# Nixie_Clock_v1_05.net
KiCad netlist of a schematic drawn in EAGLE
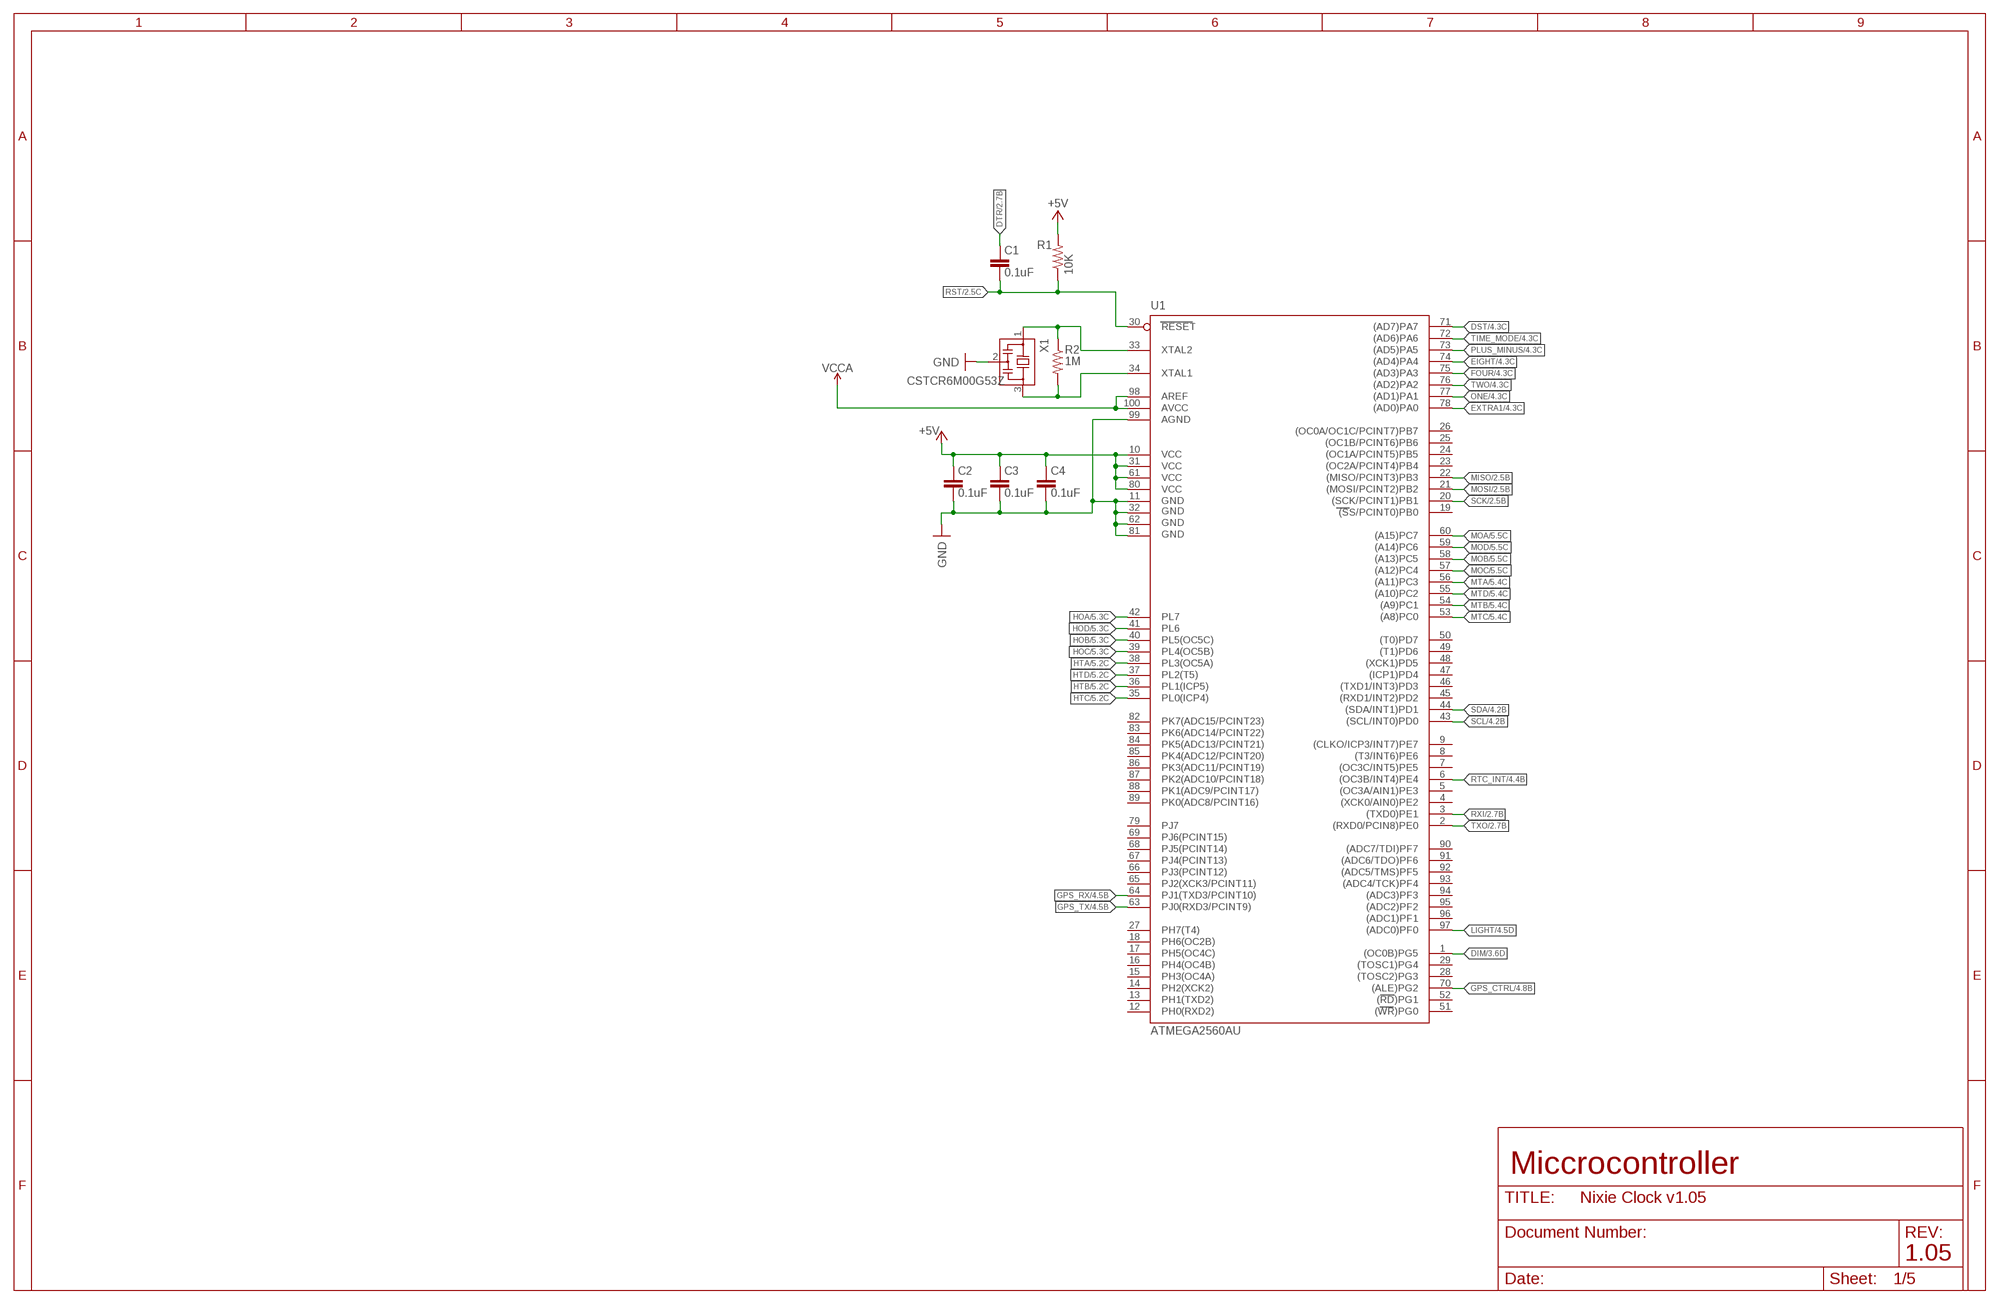
[diagram p0: schematic, sheet 1]
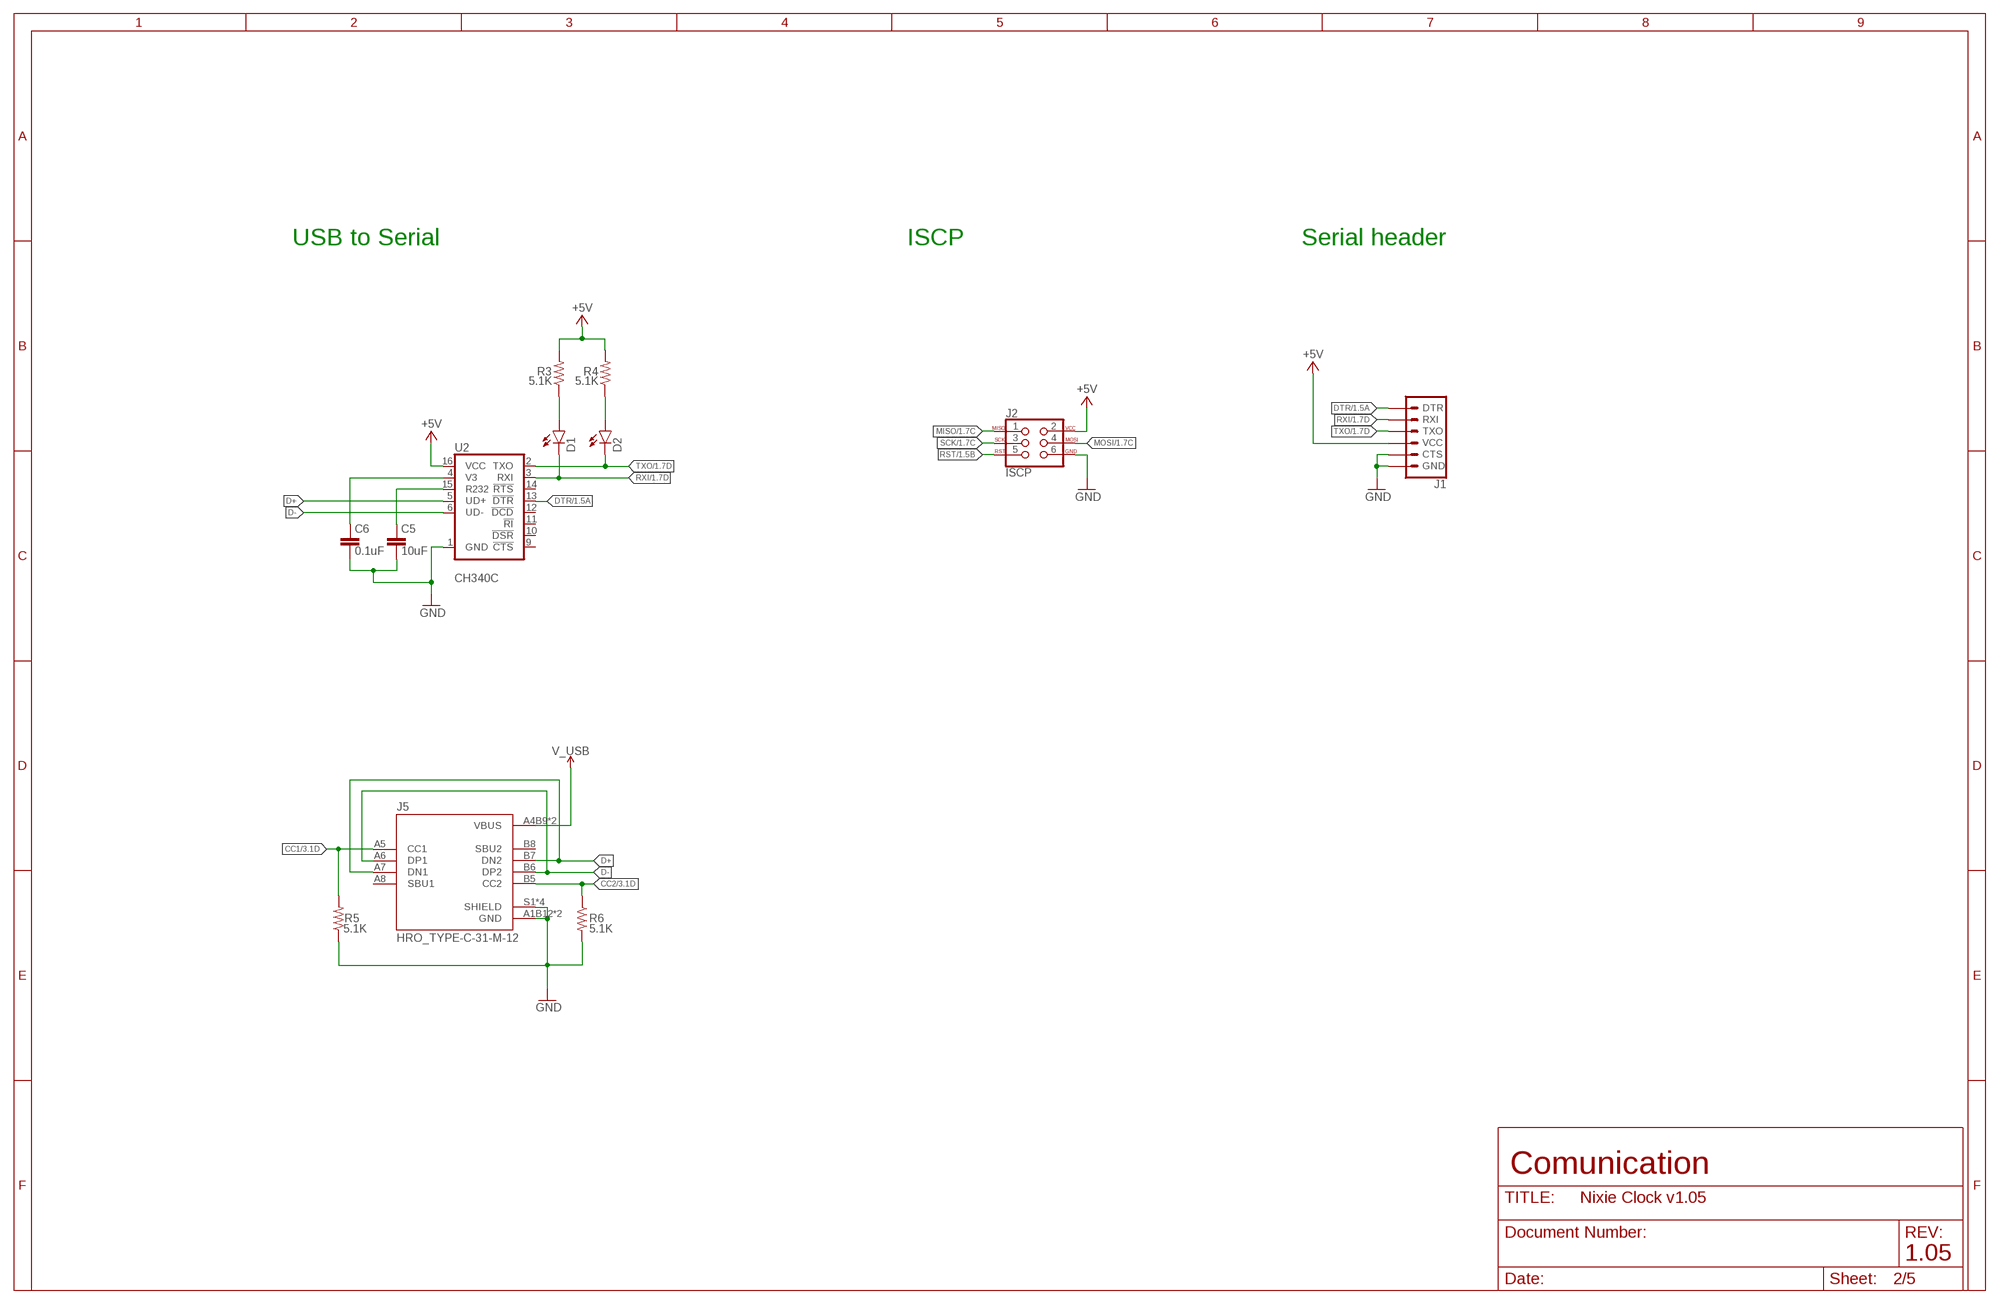
[diagram p1: schematic, sheet 2]
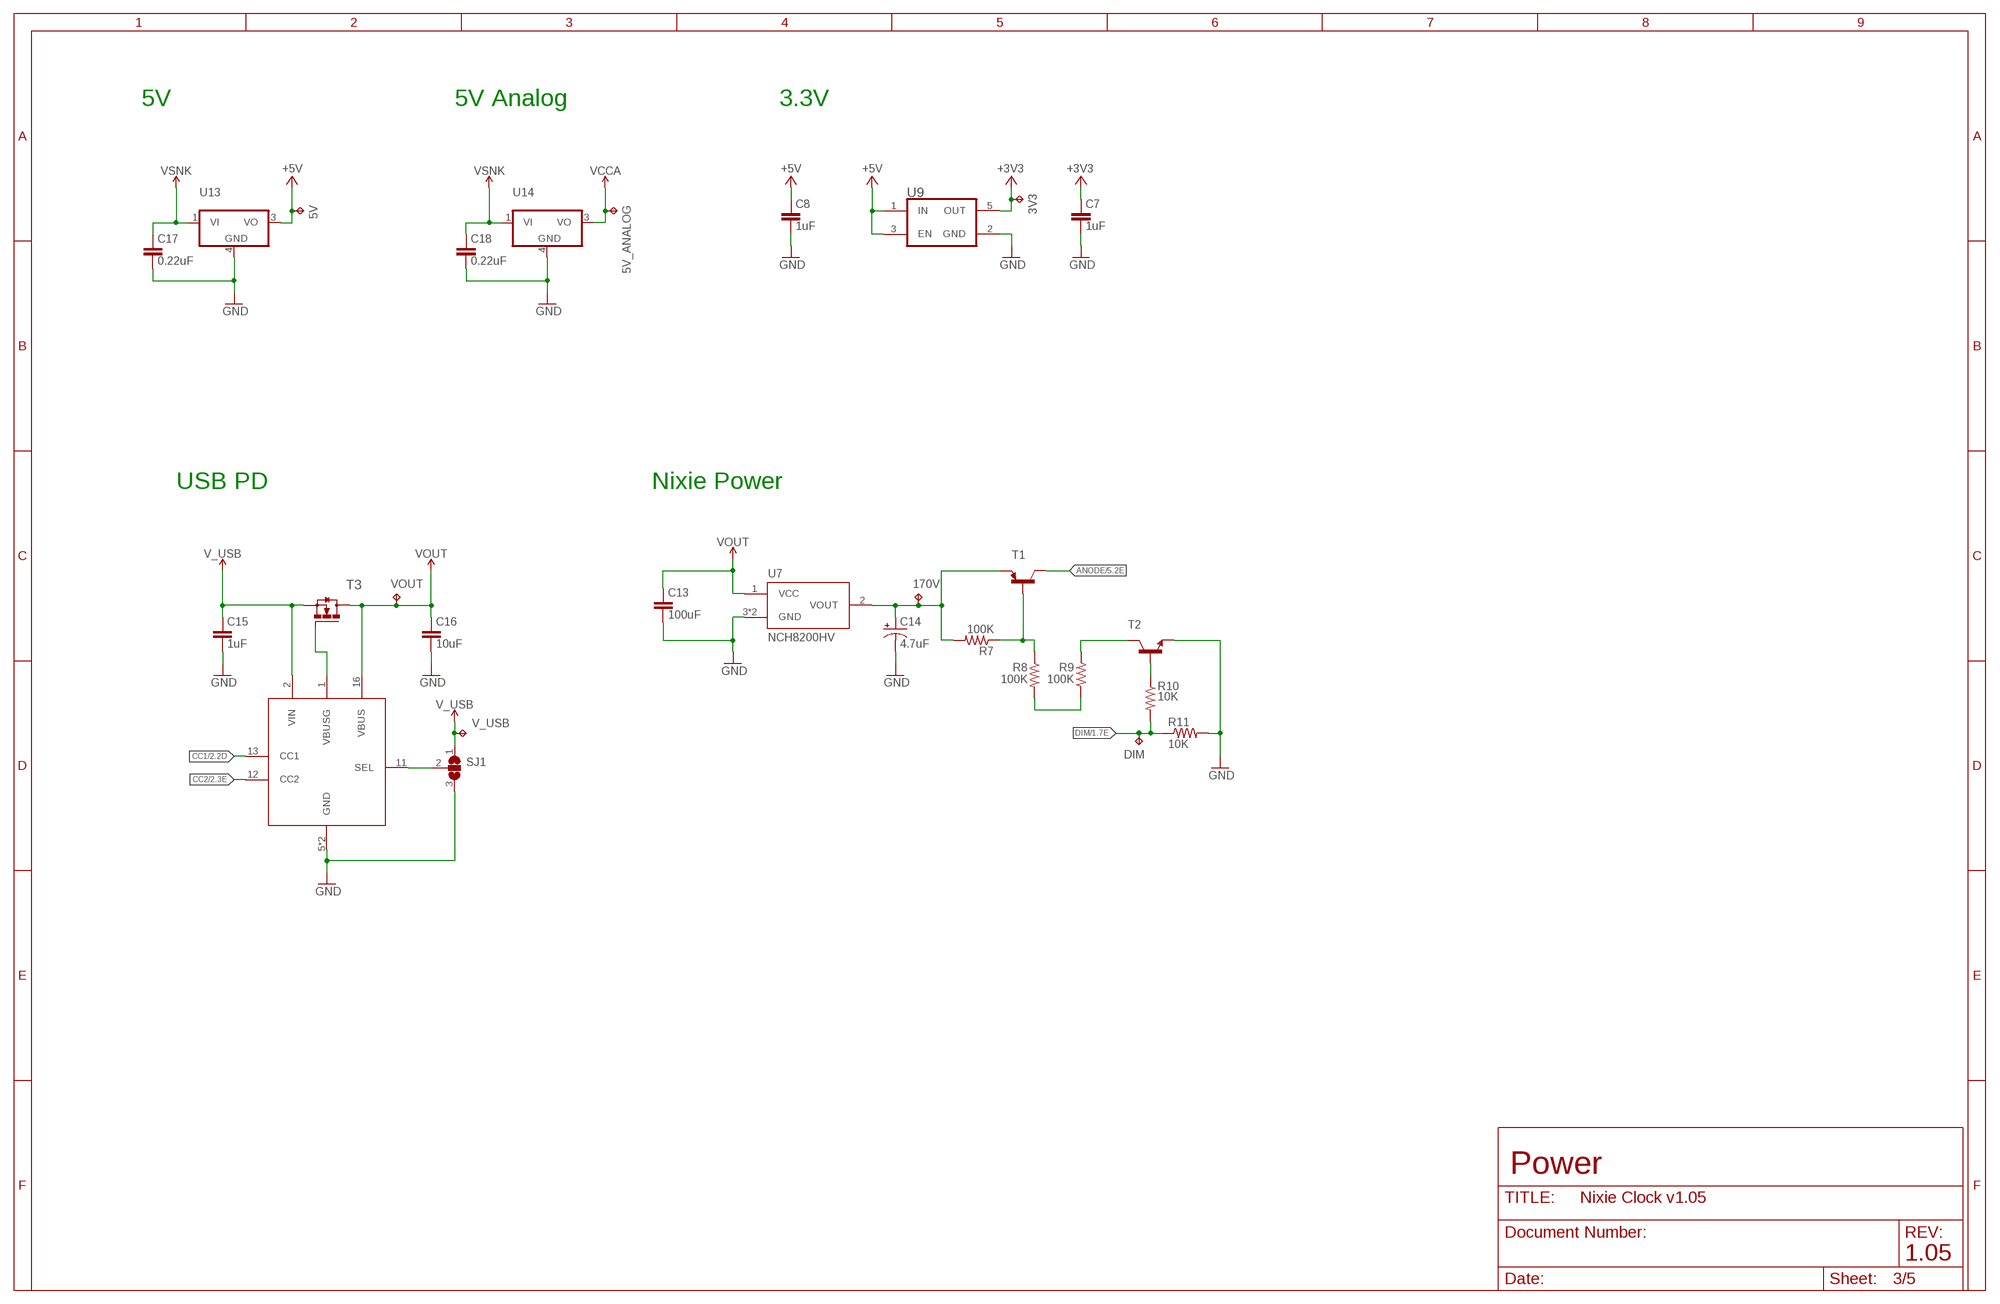
[diagram p2: schematic, sheet 3]
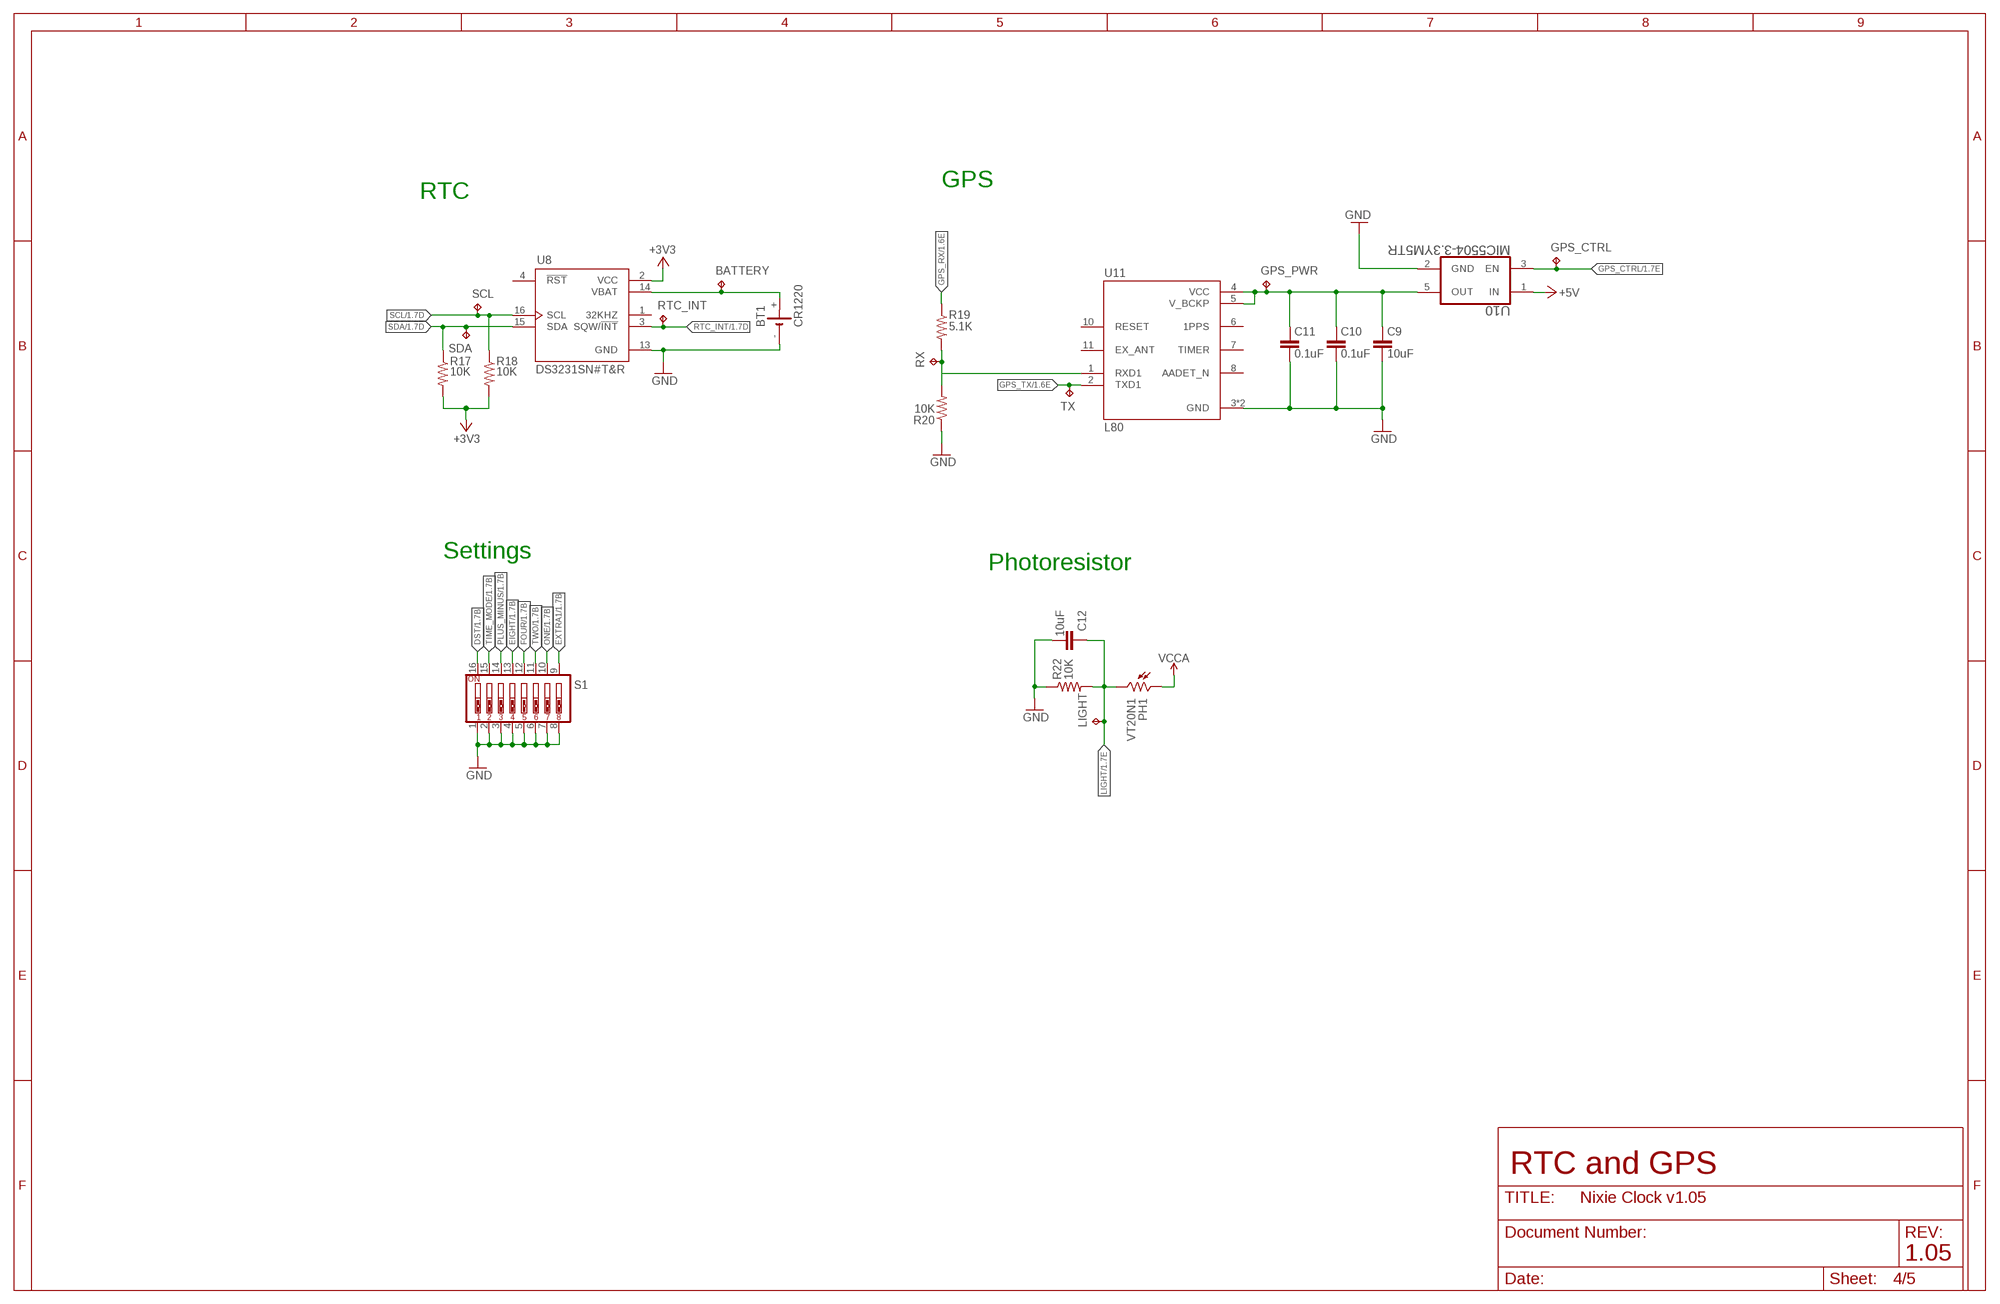
[diagram p3: schematic, sheet 4]
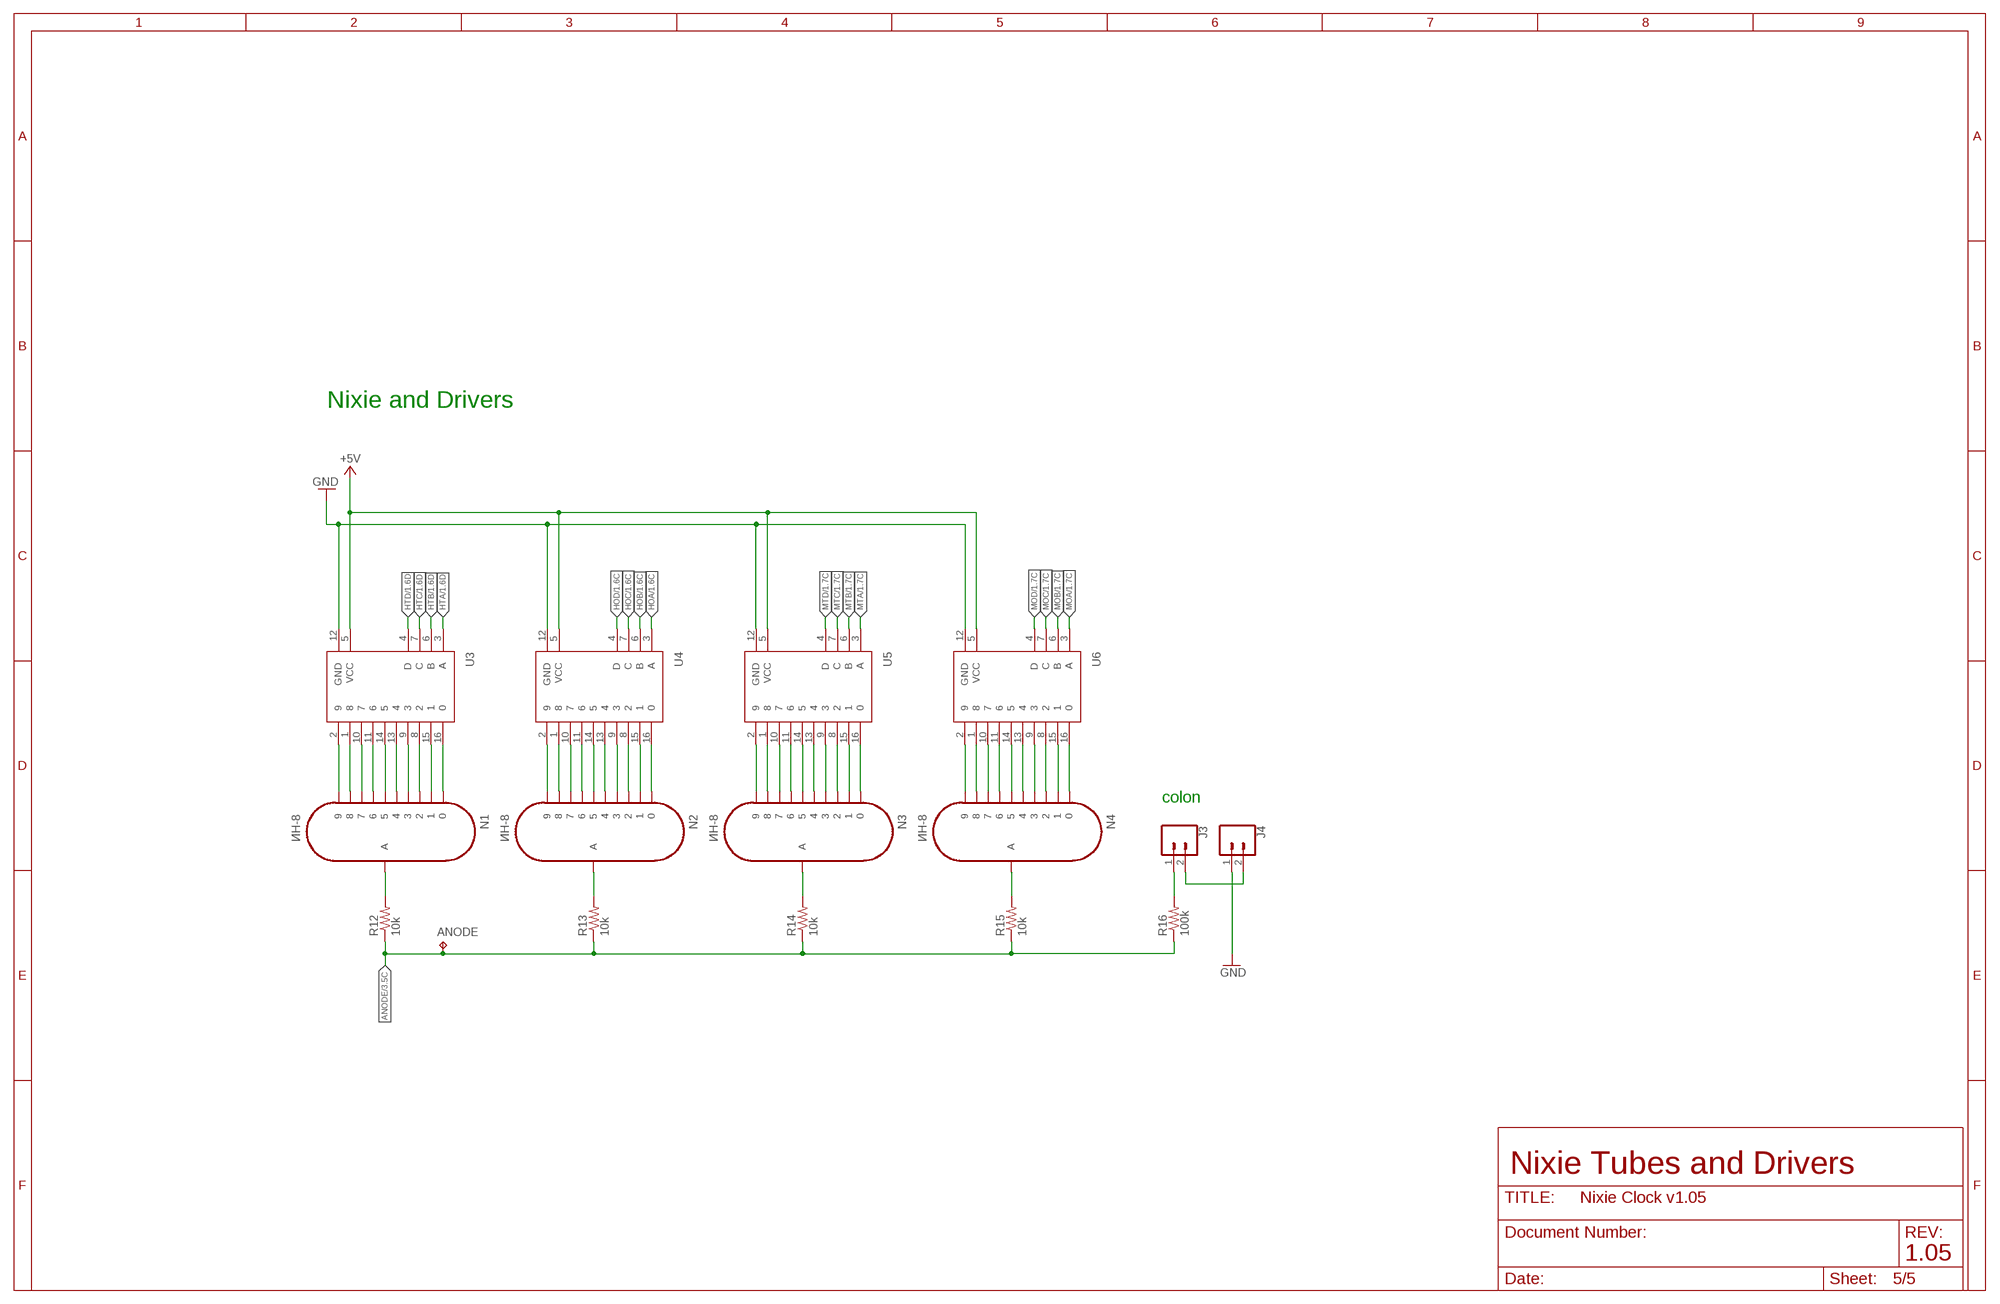
[diagram p4: schematic, sheet 5]

(export (version "E")
  (design (tool "Eeschema 10.0.6"))
  (components
    (comp (ref "ANODE")
      (value "TPPAD1-13")
      (footprint "eagle-import:P1-13")
      (libsource (lib "eagle-import") (part "TPPAD1-13"))
    )
    (comp (ref "J3")
      (value "CONN_02LOCK_LONGPADS")
      (footprint "eagle-import:1X02_LOCK_LONGPADS")
      (libsource (lib "eagle-import") (part "CONN_02LOCK_LONGPADS"))
    )
    (comp (ref "J4")
      (value "CONN_02LOCK_LONGPADS")
      (footprint "eagle-import:1X02_LOCK_LONGPADS")
      (libsource (lib "eagle-import") (part "CONN_02LOCK_LONGPADS"))
    )
    (comp (ref "N1")
      (value "ИН-8")
      (footprint "eagle-import:IN-8_SOCKET")
      (libsource (lib "eagle-import") (part "IN-8IN-8_SOCKET"))
    )
    (comp (ref "N2")
      (value "ИН-8")
      (footprint "eagle-import:IN-8_SOCKET")
      (libsource (lib "eagle-import") (part "IN-8IN-8_SOCKET"))
    )
    (comp (ref "N3")
      (value "ИН-8")
      (footprint "eagle-import:IN-8_SOCKET")
      (libsource (lib "eagle-import") (part "IN-8IN-8_SOCKET"))
    )
    (comp (ref "N4")
      (value "ИН-8")
      (footprint "eagle-import:IN-8_SOCKET")
      (libsource (lib "eagle-import") (part "IN-8IN-8_SOCKET"))
    )
    (comp (ref "R12")
      (value "10k")
      (footprint "eagle-import:M0805")
      (libsource (lib "eagle-import") (part "R-US_M0805"))
    )
    (comp (ref "R13")
      (value "10k")
      (footprint "eagle-import:M0805")
      (libsource (lib "eagle-import") (part "R-US_M0805"))
    )
    (comp (ref "R14")
      (value "10k")
      (footprint "eagle-import:M0805")
      (libsource (lib "eagle-import") (part "R-US_M0805"))
    )
    (comp (ref "R15")
      (value "10k")
      (footprint "eagle-import:M0805")
      (libsource (lib "eagle-import") (part "R-US_M0805"))
    )
    (comp (ref "R16")
      (value "100k")
      (footprint "eagle-import:R0603")
      (libsource (lib "eagle-import") (part "R-US_R0603"))
    )
    (comp (ref "U3")
      (value "K155ID1")
      (footprint "eagle-import:DIL16-KIT")
      (libsource (lib "eagle-import") (part "K155ID1"))
    )
    (comp (ref "U4")
      (value "K155ID1")
      (footprint "eagle-import:DIL16-KIT")
      (libsource (lib "eagle-import") (part "K155ID1"))
    )
    (comp (ref "U5")
      (value "K155ID1")
      (footprint "eagle-import:DIL16-KIT")
      (libsource (lib "eagle-import") (part "K155ID1"))
    )
    (comp (ref "U6")
      (value "K155ID1")
      (footprint "eagle-import:DIL16-KIT")
      (libsource (lib "eagle-import") (part "K155ID1"))
    )
    (comp (ref "C5")
      (value "10uF")
      (footprint "eagle-import:C0603")
      (libsource (lib "eagle-import") (part "C-EUC0603"))
    )
    (comp (ref "C6")
      (value "0.1uF")
      (footprint "eagle-import:C0603")
      (libsource (lib "eagle-import") (part "C-EUC0603"))
    )
    (comp (ref "D1")
      (value "LEDCHIP-LED0603")
      (footprint "eagle-import:CHIP-LED0603")
      (libsource (lib "eagle-import") (part "LEDCHIP-LED0603"))
    )
    (comp (ref "D2")
      (value "LEDCHIP-LED0603")
      (footprint "eagle-import:CHIP-LED0603")
      (libsource (lib "eagle-import") (part "LEDCHIP-LED0603"))
    )
    (comp (ref "J1")
      (value "6_PIN_SERIAL_TARGETSILK")
      (footprint "eagle-import:6_PIN_SERIAL_TARGET_SIDE_W_SILK")
      (libsource (lib "eagle-import") (part "6_PIN_SERIAL_TARGETSILK"))
    )
    (comp (ref "J2")
      (value "ISCP")
      (footprint "eagle-import:2X3")
      (libsource (lib "eagle-import") (part "AVR_SPI_PROG_3X2PTH"))
    )
    (comp (ref "J5")
      (value "HRO_TYPE-C-31-M-12")
      (footprint "eagle-import:HRO_TYPE-C-31-M-12")
      (fields (field (name "MF") "HRO Electronics Co., Ltd.") (field (name "MP") "TYPE-C-31-M-12"))
      (libsource (lib "eagle-import") (part "HRO_TYPE-C-31-M-12"))
    )
    (comp (ref "R3")
      (value "5.1K")
      (footprint "eagle-import:R0603")
      (libsource (lib "eagle-import") (part "R-US_R0603"))
    )
    (comp (ref "R4")
      (value "5.1K")
      (footprint "eagle-import:R0603")
      (libsource (lib "eagle-import") (part "R-US_R0603"))
    )
    (comp (ref "R5")
      (value "5.1K")
      (footprint "eagle-import:R0603")
      (libsource (lib "eagle-import") (part "R-US_R0603"))
    )
    (comp (ref "R6")
      (value "5.1K")
      (footprint "eagle-import:R0603")
      (libsource (lib "eagle-import") (part "R-US_R0603"))
    )
    (comp (ref "U2")
      (value "CH340C")
      (footprint "eagle-import:SO016")
      (libsource (lib "eagle-import") (part "CH340C"))
    )
    (comp (ref "BATTERY")
      (value "TPPAD1-13")
      (footprint "eagle-import:P1-13")
      (libsource (lib "eagle-import") (part "TPPAD1-13"))
    )
    (comp (ref "BT1")
      (value "CR1220")
      (footprint "eagle-import:CH291-1220LF")
      (libsource (lib "eagle-import") (part "CH291-1220LF"))
    )
    (comp (ref "C9")
      (value "10uF")
      (footprint "eagle-import:C0603")
      (libsource (lib "eagle-import") (part "C-EUC0603"))
    )
    (comp (ref "C10")
      (value "0.1uF")
      (footprint "eagle-import:C0603")
      (libsource (lib "eagle-import") (part "C-EUC0603"))
    )
    (comp (ref "C11")
      (value "0.1uF")
      (footprint "eagle-import:C0603")
      (libsource (lib "eagle-import") (part "C-EUC0603"))
    )
    (comp (ref "C12")
      (value "10uF")
      (footprint "eagle-import:C0603")
      (libsource (lib "eagle-import") (part "C-EUC0603"))
    )
    (comp (ref "GPS_CTRL")
      (value "TPPAD1-13")
      (footprint "eagle-import:P1-13")
      (libsource (lib "eagle-import") (part "TPPAD1-13"))
    )
    (comp (ref "GPS_PWR")
      (value "TPPAD1-13")
      (footprint "eagle-import:P1-13")
      (libsource (lib "eagle-import") (part "TPPAD1-13"))
    )
    (comp (ref "LIGHT")
      (value "TPPAD1-13")
      (footprint "eagle-import:P1-13")
      (libsource (lib "eagle-import") (part "TPPAD1-13"))
    )
    (comp (ref "PH1")
      (value "VT20N1")
      (footprint "eagle-import:TO46-VT200")
      (libsource (lib "eagle-import") (part "VT20N1"))
    )
    (comp (ref "R17")
      (value "10K")
      (footprint "eagle-import:R0603")
      (libsource (lib "eagle-import") (part "R-US_R0603"))
    )
    (comp (ref "R18")
      (value "10K")
      (footprint "eagle-import:R0603")
      (libsource (lib "eagle-import") (part "R-US_R0603"))
    )
    (comp (ref "R19")
      (value "5.1K")
      (footprint "eagle-import:R0603")
      (libsource (lib "eagle-import") (part "R-US_R0603"))
    )
    (comp (ref "R20")
      (value "10K")
      (footprint "eagle-import:R0603")
      (libsource (lib "eagle-import") (part "R-US_R0603"))
    )
    (comp (ref "R22")
      (value "10K")
      (footprint "eagle-import:R0603")
      (libsource (lib "eagle-import") (part "R-US_R0603"))
    )
    (comp (ref "RTC_INT")
      (value "TPPAD1-13")
      (footprint "eagle-import:P1-13")
      (libsource (lib "eagle-import") (part "TPPAD1-13"))
    )
    (comp (ref "RX")
      (value "TPPAD1-13")
      (footprint "eagle-import:P1-13")
      (libsource (lib "eagle-import") (part "TPPAD1-13"))
    )
    (comp (ref "S1")
      (value "SW_DIP-8")
      (footprint "eagle-import:EDG-08")
      (libsource (lib "eagle-import") (part "SW_DIP-8"))
    )
    (comp (ref "SCL")
      (value "TPPAD1-13")
      (footprint "eagle-import:P1-13")
      (libsource (lib "eagle-import") (part "TPPAD1-13"))
    )
    (comp (ref "SDA")
      (value "TPPAD1-13")
      (footprint "eagle-import:P1-13")
      (libsource (lib "eagle-import") (part "TPPAD1-13"))
    )
    (comp (ref "TX")
      (value "TPPAD1-13")
      (footprint "eagle-import:P1-13")
      (libsource (lib "eagle-import") (part "TPPAD1-13"))
    )
    (comp (ref "U8")
      (value "DS3231SN#T&R")
      (footprint "eagle-import:SOIC127P1032X265-16N")
      (fields (field (name "MF") "Maxim Integrated") (field (name "MP") "DS3231SN#T&amp;R"))
      (libsource (lib "eagle-import") (part "DS3231SN#T&R"))
    )
    (comp (ref "U10")
      (value "MIC5504-3.3YM5TR")
      (footprint "eagle-import:SOT95P280X130-5N")
      (fields (field (name "MPN") "MIC5504-3.3YM5-TR"))
      (libsource (lib "eagle-import") (part "MIC5504-3.3YM5TR"))
    )
    (comp (ref "U11")
      (value "L80")
      (footprint "eagle-import:XCVR_L80")
      (fields (field (name "MF") "Quectel") (field (name "MP") "L80-M39"))
      (libsource (lib "eagle-import") (part "L80"))
    )
    (comp (ref "C1")
      (value "0.1uF")
      (footprint "eagle-import:C0603")
      (libsource (lib "eagle-import") (part "C-EUC0603"))
    )
    (comp (ref "C2")
      (value "0.1uF")
      (footprint "eagle-import:C0603")
      (libsource (lib "eagle-import") (part "C-EUC0603"))
    )
    (comp (ref "C3")
      (value "0.1uF")
      (footprint "eagle-import:C0603")
      (libsource (lib "eagle-import") (part "C-EUC0603"))
    )
    (comp (ref "C4")
      (value "0.1uF")
      (footprint "eagle-import:C0603")
      (libsource (lib "eagle-import") (part "C-EUC0603"))
    )
    (comp (ref "R1")
      (value "10K")
      (footprint "eagle-import:R0603")
      (libsource (lib "eagle-import") (part "R-US_R0603"))
    )
    (comp (ref "R2")
      (value "1M")
      (footprint "eagle-import:R0603")
      (libsource (lib "eagle-import") (part "R-US_R0603"))
    )
    (comp (ref "U1")
      (value "ATMEGA2560AU")
      (footprint "eagle-import:TQFP100")
      (fields (field (name "MPN") "ATMEGA2560-16AU"))
      (libsource (lib "eagle-import") (part "ATMEGA2560AU"))
    )
    (comp (ref "X1")
      (value "CSTCR6M00G53Z")
      (footprint "eagle-import:CSTCR6M")
      (fields (field (name "MPN") "CSTCR6M00G53-R0") (field (name "MPN_1") "CSTCE16M0V13C99-R0"))
      (libsource (lib "eagle-import") (part "CSTCR6M00G53Z"))
    )
    (comp (ref "3V3")
      (value "TPPAD1-13")
      (footprint "eagle-import:P1-13")
      (libsource (lib "eagle-import") (part "TPPAD1-13"))
    )
    (comp (ref "5V")
      (value "TPPAD1-13")
      (footprint "eagle-import:P1-13")
      (libsource (lib "eagle-import") (part "TPPAD1-13"))
    )
    (comp (ref "5V_ANALOG")
      (value "TPPAD1-13")
      (footprint "eagle-import:P1-13")
      (libsource (lib "eagle-import") (part "TPPAD1-13"))
    )
    (comp (ref "170V")
      (value "TPPAD1-13")
      (footprint "eagle-import:P1-13")
      (libsource (lib "eagle-import") (part "TPPAD1-13"))
    )
    (comp (ref "C7")
      (value "1uF")
      (footprint "eagle-import:C0603")
      (libsource (lib "eagle-import") (part "C-EUC0603"))
    )
    (comp (ref "C8")
      (value "1uF")
      (footprint "eagle-import:C0603")
      (libsource (lib "eagle-import") (part "C-EUC0603"))
    )
    (comp (ref "C13")
      (value "100uF")
      (footprint "eagle-import:C0603")
      (libsource (lib "eagle-import") (part "C-EUC0603"))
    )
    (comp (ref "C14")
      (value "4.7uF")
      (footprint "eagle-import:E3,5-8")
      (libsource (lib "eagle-import") (part "CPOL-USE3.5-8"))
    )
    (comp (ref "C15")
      (value "1uF")
      (footprint "eagle-import:C0603")
      (libsource (lib "eagle-import") (part "C-EUC0603"))
    )
    (comp (ref "C16")
      (value "10uF")
      (footprint "eagle-import:C0603")
      (libsource (lib "eagle-import") (part "C-EUC0603"))
    )
    (comp (ref "C17")
      (value "0.22uF")
      (footprint "eagle-import:C0603")
      (libsource (lib "eagle-import") (part "C-EUC0603"))
    )
    (comp (ref "C18")
      (value "0.22uF")
      (footprint "eagle-import:C0603")
      (libsource (lib "eagle-import") (part "C-EUC0603"))
    )
    (comp (ref "DIM")
      (value "TPPAD1-13")
      (footprint "eagle-import:P1-13")
      (libsource (lib "eagle-import") (part "TPPAD1-13"))
    )
    (comp (ref "R7")
      (value "100K")
      (footprint "eagle-import:R0603")
      (libsource (lib "eagle-import") (part "R-US_R0603"))
    )
    (comp (ref "R8")
      (value "100K")
      (footprint "eagle-import:R0603")
      (libsource (lib "eagle-import") (part "R-US_R0603"))
    )
    (comp (ref "R9")
      (value "100K")
      (footprint "eagle-import:R0603")
      (libsource (lib "eagle-import") (part "R-US_R0603"))
    )
    (comp (ref "R10")
      (value "10K")
      (footprint "eagle-import:R0603")
      (libsource (lib "eagle-import") (part "R-US_R0603"))
    )
    (comp (ref "R11")
      (value "10K")
      (footprint "eagle-import:R0603")
      (libsource (lib "eagle-import") (part "R-US_R0603"))
    )
    (comp (ref "SJ1")
      (value "SJ2W")
      (footprint "eagle-import:SJ_2")
      (libsource (lib "eagle-import") (part "SJ2W"))
    )
    (comp (ref "T1")
      (value "PZTA92")
      (footprint "eagle-import:SOT223")
      (libsource (lib "eagle-import") (part "PZTA92"))
    )
    (comp (ref "T2")
      (value "PZTA42")
      (footprint "eagle-import:SOT223")
      (libsource (lib "eagle-import") (part "PZTA42"))
    )
    (comp (ref "T3")
      (value "CSD18543Q3A")
      (footprint "eagle-import:VSONP-8")
      (fields (field (name "MFR") "TI"))
      (libsource (lib "eagle-import") (part "CSD18543Q3A"))
    )
    (comp (ref "U7")
      (value "NCH8200HV")
      (footprint "eagle-import:NCH8200HV")
      (libsource (lib "eagle-import") (part "NCH8200HV"))
    )
    (comp (ref "U9")
      (value "MIC5504-3.3YM5TR")
      (footprint "eagle-import:SOT95P280X130-5N")
      (fields (field (name "MPN") "MIC5504-3.3YM5-TR"))
      (libsource (lib "eagle-import") (part "MIC5504-3.3YM5TR"))
    )
    (comp (ref "U12")
      (value "IP2721")
      (footprint "eagle-import:TSSOP16EXP")
      (libsource (lib "eagle-import") (part "IP2721"))
    )
    (comp (ref "U13")
      (value "LM340MP-05")
      (footprint "eagle-import:SOT223")
      (fields (field (name "MFR") "TI") (field (name "MPN") "LM340MP-5.0/NOPB"))
      (libsource (lib "eagle-import") (part "LM340?-MP05"))
    )
    (comp (ref "U14")
      (value "LM340MP-05")
      (footprint "eagle-import:SOT223")
      (libsource (lib "eagle-import") (part "LM340?-MP05"))
    )
    (comp (ref "VOUT")
      (value "TPPAD1-13")
      (footprint "eagle-import:P1-13")
      (libsource (lib "eagle-import") (part "TPPAD1-13"))
    )
    (comp (ref "V_USB")
      (value "TPPAD1-13")
      (footprint "eagle-import:P1-13")
      (libsource (lib "eagle-import") (part "TPPAD1-13"))
    )
  )
  (nets
    (net (code "1") (name "+3V3") (class "Default")
      (node (ref "3V3") (pin "TP") (pinfunction "TP_TP") (pintype "input"))
      (node (ref "C7") (pin "1") (pinfunction "1_1") (pintype "passive"))
      (node (ref "R17") (pin "2") (pinfunction "2_2") (pintype "passive"))
      (node (ref "R18") (pin "2") (pinfunction "2_2") (pintype "passive"))
      (node (ref "U8") (pin "2") (pinfunction "VCC_2") (pintype "power_in"))
      (node (ref "U9") (pin "5") (pinfunction "OUT_5") (pintype "output"))
    )
    (net (code "2") (name "+5V") (class "Default")
      (node (ref "5V") (pin "TP") (pinfunction "TP_TP") (pintype "input"))
      (node (ref "C2") (pin "1") (pinfunction "1_1") (pintype "passive"))
      (node (ref "C3") (pin "1") (pinfunction "1_1") (pintype "passive"))
      (node (ref "C4") (pin "1") (pinfunction "1_1") (pintype "passive"))
      (node (ref "C8") (pin "1") (pinfunction "1_1") (pintype "passive"))
      (node (ref "J1") (pin "P$4") (pinfunction "VCC_P$4") (pintype "passive"))
      (node (ref "J2") (pin "2") (pinfunction "2_2") (pintype "passive"))
      (node (ref "R1") (pin "2") (pinfunction "2_2") (pintype "passive"))
      (node (ref "R3") (pin "2") (pinfunction "2_2") (pintype "passive"))
      (node (ref "R4") (pin "2") (pinfunction "2_2") (pintype "passive"))
      (node (ref "U1") (pin "10") (pinfunction "VCC_10") (pintype "power_in"))
      (node (ref "U1") (pin "31") (pinfunction "VCC1_31") (pintype "power_in"))
      (node (ref "U1") (pin "61") (pinfunction "VCC2_61") (pintype "power_in"))
      (node (ref "U1") (pin "80") (pinfunction "VCC3_80") (pintype "power_in"))
      (node (ref "U10") (pin "1") (pinfunction "IN_1") (pintype "input"))
      (node (ref "U13") (pin "3") (pinfunction "VO_3") (pintype "passive"))
      (node (ref "U2") (pin "16") (pinfunction "VCC_16") (pintype "bidirectional"))
      (node (ref "U3") (pin "5") (pinfunction "VCC_5") (pintype "bidirectional"))
      (node (ref "U4") (pin "5") (pinfunction "VCC_5") (pintype "bidirectional"))
      (node (ref "U5") (pin "5") (pinfunction "VCC_5") (pintype "bidirectional"))
      (node (ref "U6") (pin "5") (pinfunction "VCC_5") (pintype "bidirectional"))
      (node (ref "U9") (pin "1") (pinfunction "IN_1") (pintype "input"))
      (node (ref "U9") (pin "3") (pinfunction "EN_3") (pintype "input"))
    )
    (net (code "3") (name "ANODE") (class "Default")
      (node (ref "ANODE") (pin "TP") (pinfunction "TP_TP") (pintype "input"))
      (node (ref "R12") (pin "1") (pinfunction "1_1") (pintype "passive"))
      (node (ref "R13") (pin "1") (pinfunction "1_1") (pintype "passive"))
      (node (ref "R14") (pin "1") (pinfunction "1_1") (pintype "passive"))
      (node (ref "R15") (pin "1") (pinfunction "1_1") (pintype "passive"))
      (node (ref "R16") (pin "1") (pinfunction "1_1") (pintype "passive"))
      (node (ref "T1") (pin "2") (pinfunction "C_2") (pintype "passive"))
      (node (ref "T1") (pin "4") (pinfunction "C_4") (pintype "passive"))
    )
    (net (code "4") (name "CC1") (class "Default")
      (node (ref "J5") (pin "A5") (pinfunction "CC1_A5") (pintype "bidirectional"))
      (node (ref "R5") (pin "2") (pinfunction "2_2") (pintype "passive"))
      (node (ref "U12") (pin "13") (pinfunction "CC1_13") (pintype "bidirectional"))
    )
    (net (code "5") (name "CC2") (class "Default")
      (node (ref "J5") (pin "B5") (pinfunction "CC2_B5") (pintype "bidirectional"))
      (node (ref "R6") (pin "1") (pinfunction "1_1") (pintype "passive"))
      (node (ref "U12") (pin "12") (pinfunction "CC2_12") (pintype "bidirectional"))
    )
    (net (code "6") (name "D+") (class "Default")
      (node (ref "J5") (pin "A7") (pinfunction "DN1_A7") (pintype "bidirectional"))
      (node (ref "J5") (pin "B7") (pinfunction "DN2_B7") (pintype "bidirectional"))
      (node (ref "U2") (pin "5") (pinfunction "UD+_5") (pintype "bidirectional"))
    )
    (net (code "7") (name "D-") (class "Default")
      (node (ref "J5") (pin "A6") (pinfunction "DP1_A6") (pintype "bidirectional"))
      (node (ref "J5") (pin "B6") (pinfunction "DP2_B6") (pintype "bidirectional"))
      (node (ref "U2") (pin "6") (pinfunction "UD-_6") (pintype "bidirectional"))
    )
    (net (code "8") (name "DIM") (class "Default")
      (node (ref "DIM") (pin "TP") (pinfunction "TP_TP") (pintype "input"))
      (node (ref "R10") (pin "2") (pinfunction "2_2") (pintype "passive"))
      (node (ref "R11") (pin "1") (pinfunction "1_1") (pintype "passive"))
      (node (ref "U1") (pin "1") (pinfunction "(OC0B)PG5_1") (pintype "bidirectional"))
    )
    (net (code "9") (name "DST") (class "Default")
      (node (ref "S1") (pin "16") (pinfunction "16_16") (pintype "passive"))
      (node (ref "U1") (pin "71") (pinfunction "(AD7)PA7_71") (pintype "bidirectional"))
    )
    (net (code "10") (name "DTR") (class "Default")
      (node (ref "C1") (pin "1") (pinfunction "1_1") (pintype "passive"))
      (node (ref "J1") (pin "P$1") (pinfunction "DTR_P$1") (pintype "passive"))
      (node (ref "U2") (pin "13") (pinfunction "~{DTR}_13") (pintype "bidirectional"))
    )
    (net (code "11") (name "EIGHT") (class "Default")
      (node (ref "S1") (pin "13") (pinfunction "13_13") (pintype "passive"))
      (node (ref "U1") (pin "74") (pinfunction "(AD4)PA4_74") (pintype "bidirectional"))
    )
    (net (code "12") (name "EXTRA1") (class "Default")
      (node (ref "S1") (pin "9") (pinfunction "9_9") (pintype "passive"))
      (node (ref "U1") (pin "78") (pinfunction "(AD0)PA0_78") (pintype "bidirectional"))
    )
    (net (code "13") (name "FOUR") (class "Default")
      (node (ref "S1") (pin "12") (pinfunction "12_12") (pintype "passive"))
      (node (ref "U1") (pin "75") (pinfunction "(AD3)PA3_75") (pintype "bidirectional"))
    )
    (net (code "14") (name "GND") (class "Default")
      (node (ref "BT1") (pin "-") (pinfunction "-_-") (pintype "passive"))
      (node (ref "C10") (pin "2") (pinfunction "2_2") (pintype "passive"))
      (node (ref "C11") (pin "2") (pinfunction "2_2") (pintype "passive"))
      (node (ref "C12") (pin "2") (pinfunction "2_2") (pintype "passive"))
      (node (ref "C13") (pin "2") (pinfunction "2_2") (pintype "passive"))
      (node (ref "C14") (pin "-") (pinfunction "-_-") (pintype "passive"))
      (node (ref "C15") (pin "2") (pinfunction "2_2") (pintype "passive"))
      (node (ref "C16") (pin "2") (pinfunction "2_2") (pintype "passive"))
      (node (ref "C17") (pin "2") (pinfunction "2_2") (pintype "passive"))
      (node (ref "C18") (pin "2") (pinfunction "2_2") (pintype "passive"))
      (node (ref "C2") (pin "2") (pinfunction "2_2") (pintype "passive"))
      (node (ref "C3") (pin "2") (pinfunction "2_2") (pintype "passive"))
      (node (ref "C4") (pin "2") (pinfunction "2_2") (pintype "passive"))
      (node (ref "C5") (pin "2") (pinfunction "2_2") (pintype "passive"))
      (node (ref "C6") (pin "2") (pinfunction "2_2") (pintype "passive"))
      (node (ref "C7") (pin "2") (pinfunction "2_2") (pintype "passive"))
      (node (ref "C8") (pin "2") (pinfunction "2_2") (pintype "passive"))
      (node (ref "C9") (pin "2") (pinfunction "2_2") (pintype "passive"))
      (node (ref "J1") (pin "P$5") (pinfunction "CTS_P$5") (pintype "passive"))
      (node (ref "J1") (pin "P$6") (pinfunction "GND_P$6") (pintype "passive"))
      (node (ref "J2") (pin "6") (pinfunction "6_6") (pintype "passive"))
      (node (ref "J4") (pin "1") (pinfunction "1_1") (pintype "passive"))
      (node (ref "J5") (pin "A1B12") (pinfunction "GND_A1B12") (pintype "power_in"))
      (node (ref "J5") (pin "B1A12") (pinfunction "GND_B1A12") (pintype "power_in"))
      (node (ref "J5") (pin "S1") (pinfunction "SHIELD_S1") (pintype "passive"))
      (node (ref "J5") (pin "S2") (pinfunction "SHIELD_S2") (pintype "passive"))
      (node (ref "J5") (pin "S3") (pinfunction "SHIELD_S3") (pintype "passive"))
      (node (ref "J5") (pin "S4") (pinfunction "SHIELD_S4") (pintype "passive"))
      (node (ref "R11") (pin "2") (pinfunction "2_2") (pintype "passive"))
      (node (ref "R20") (pin "1") (pinfunction "1_1") (pintype "passive"))
      (node (ref "R22") (pin "1") (pinfunction "1_1") (pintype "passive"))
      (node (ref "R5") (pin "1") (pinfunction "1_1") (pintype "passive"))
      (node (ref "R6") (pin "2") (pinfunction "2_2") (pintype "passive"))
      (node (ref "S1") (pin "1") (pinfunction "1_1") (pintype "passive"))
      (node (ref "S1") (pin "2") (pinfunction "2_2") (pintype "passive"))
      (node (ref "S1") (pin "3") (pinfunction "3_3") (pintype "passive"))
      (node (ref "S1") (pin "4") (pinfunction "4_4") (pintype "passive"))
      (node (ref "S1") (pin "5") (pinfunction "5_5") (pintype "passive"))
      (node (ref "S1") (pin "6") (pinfunction "6_6") (pintype "passive"))
      (node (ref "S1") (pin "7") (pinfunction "7_7") (pintype "passive"))
      (node (ref "S1") (pin "8") (pinfunction "8_8") (pintype "passive"))
      (node (ref "SJ1") (pin "3") (pinfunction "3_3") (pintype "passive"))
      (node (ref "T2") (pin "3") (pinfunction "E_3") (pintype "passive"))
      (node (ref "U1") (pin "11") (pinfunction "GND_11") (pintype "power_in"))
      (node (ref "U1") (pin "32") (pinfunction "GND1_32") (pintype "power_in"))
      (node (ref "U1") (pin "62") (pinfunction "GND2_62") (pintype "power_in"))
      (node (ref "U1") (pin "81") (pinfunction "GND3_81") (pintype "power_in"))
      (node (ref "U1") (pin "99") (pinfunction "AGND_99") (pintype "power_in"))
      (node (ref "U10") (pin "2") (pinfunction "GND_2") (pintype "passive"))
      (node (ref "U11") (pin "12") (pinfunction "GND_12") (pintype "power_in"))
      (node (ref "U11") (pin "3") (pinfunction "GND_3") (pintype "power_in"))
      (node (ref "U12") (pin "5") (pinfunction "GND_5") (pintype "bidirectional"))
      (node (ref "U12") (pin "EXP") (pinfunction "GND_EXP") (pintype "bidirectional"))
      (node (ref "U13") (pin "4") (pinfunction "GND_4") (pintype "passive"))
      (node (ref "U14") (pin "4") (pinfunction "GND_4") (pintype "passive"))
      (node (ref "U2") (pin "1") (pinfunction "GND_1") (pintype "bidirectional"))
      (node (ref "U3") (pin "12") (pinfunction "GND_12") (pintype "bidirectional"))
      (node (ref "U4") (pin "12") (pinfunction "GND_12") (pintype "bidirectional"))
      (node (ref "U5") (pin "12") (pinfunction "GND_12") (pintype "bidirectional"))
      (node (ref "U6") (pin "12") (pinfunction "GND_12") (pintype "bidirectional"))
      (node (ref "U7") (pin "3") (pinfunction "GND_3") (pintype "bidirectional"))
      (node (ref "U7") (pin "4") (pinfunction "GND_4") (pintype "bidirectional"))
      (node (ref "U8") (pin "13") (pinfunction "GND_13") (pintype "power_in"))
      (node (ref "U9") (pin "2") (pinfunction "GND_2") (pintype "passive"))
      (node (ref "X1") (pin "2") (pinfunction "2_2") (pintype "passive"))
    )
    (net (code "15") (name "GPS_CTRL") (class "Default")
      (node (ref "GPS_CTRL") (pin "TP") (pinfunction "TP_TP") (pintype "input"))
      (node (ref "U1") (pin "70") (pinfunction "(ALE)PG2_70") (pintype "bidirectional"))
      (node (ref "U10") (pin "3") (pinfunction "EN_3") (pintype "input"))
    )
    (net (code "16") (name "GPS_RX") (class "Default")
      (node (ref "R19") (pin "1") (pinfunction "1_1") (pintype "passive"))
      (node (ref "U1") (pin "64") (pinfunction "PJ1(TXD3/PCINT10)_64") (pintype "bidirectional"))
    )
    (net (code "17") (name "GPS_TX") (class "Default")
      (node (ref "TX") (pin "TP") (pinfunction "TP_TP") (pintype "input"))
      (node (ref "U1") (pin "63") (pinfunction "PJ0(RXD3/PCINT9)_63") (pintype "bidirectional"))
      (node (ref "U11") (pin "2") (pinfunction "TXD1_2") (pintype "output"))
    )
    (net (code "18") (name "HOA") (class "Default")
      (node (ref "U1") (pin "42") (pinfunction "PL7_42") (pintype "bidirectional"))
      (node (ref "U4") (pin "3") (pinfunction "A_3") (pintype "input"))
    )
    (net (code "19") (name "HOB") (class "Default")
      (node (ref "U1") (pin "40") (pinfunction "PL5(OC5C)_40") (pintype "bidirectional"))
      (node (ref "U4") (pin "6") (pinfunction "B_6") (pintype "input"))
    )
    (net (code "20") (name "HOC") (class "Default")
      (node (ref "U1") (pin "39") (pinfunction "PL4(OC5B)_39") (pintype "bidirectional"))
      (node (ref "U4") (pin "7") (pinfunction "C_7") (pintype "input"))
    )
    (net (code "21") (name "HOD") (class "Default")
      (node (ref "U1") (pin "41") (pinfunction "PL6_41") (pintype "bidirectional"))
      (node (ref "U4") (pin "4") (pinfunction "D_4") (pintype "input"))
    )
    (net (code "22") (name "HTA") (class "Default")
      (node (ref "U1") (pin "38") (pinfunction "PL3(OC5A)_38") (pintype "bidirectional"))
      (node (ref "U3") (pin "3") (pinfunction "A_3") (pintype "input"))
    )
    (net (code "23") (name "HTB") (class "Default")
      (node (ref "U1") (pin "36") (pinfunction "PL1(ICP5)_36") (pintype "bidirectional"))
      (node (ref "U3") (pin "6") (pinfunction "B_6") (pintype "input"))
    )
    (net (code "24") (name "HTC") (class "Default")
      (node (ref "U1") (pin "35") (pinfunction "PL0(ICP4)_35") (pintype "bidirectional"))
      (node (ref "U3") (pin "7") (pinfunction "C_7") (pintype "input"))
    )
    (net (code "25") (name "HTD") (class "Default")
      (node (ref "U1") (pin "37") (pinfunction "PL2(T5)_37") (pintype "bidirectional"))
      (node (ref "U3") (pin "4") (pinfunction "D_4") (pintype "input"))
    )
    (net (code "26") (name "LIGHT") (class "Default")
      (node (ref "C12") (pin "1") (pinfunction "1_1") (pintype "passive"))
      (node (ref "LIGHT") (pin "TP") (pinfunction "TP_TP") (pintype "input"))
      (node (ref "PH1") (pin "2") (pinfunction "2_2") (pintype "passive"))
      (node (ref "R22") (pin "2") (pinfunction "2_2") (pintype "passive"))
      (node (ref "U1") (pin "97") (pinfunction "(ADC0)PF0_97") (pintype "bidirectional"))
    )
    (net (code "27") (name "MISO") (class "Default")
      (node (ref "J2") (pin "1") (pinfunction "1_1") (pintype "passive"))
      (node (ref "U1") (pin "22") (pinfunction "(MISO/PCINT3)PB3_22") (pintype "bidirectional"))
    )
    (net (code "28") (name "MOA") (class "Default")
      (node (ref "U1") (pin "60") (pinfunction "(A15)PC7_60") (pintype "bidirectional"))
      (node (ref "U6") (pin "3") (pinfunction "A_3") (pintype "input"))
    )
    (net (code "29") (name "MOB") (class "Default")
      (node (ref "U1") (pin "58") (pinfunction "(A13)PC5_58") (pintype "bidirectional"))
      (node (ref "U6") (pin "6") (pinfunction "B_6") (pintype "input"))
    )
    (net (code "30") (name "MOC") (class "Default")
      (node (ref "U1") (pin "57") (pinfunction "(A12)PC4_57") (pintype "bidirectional"))
      (node (ref "U6") (pin "7") (pinfunction "C_7") (pintype "input"))
    )
    (net (code "31") (name "MOD") (class "Default")
      (node (ref "U1") (pin "59") (pinfunction "(A14)PC6_59") (pintype "bidirectional"))
      (node (ref "U6") (pin "4") (pinfunction "D_4") (pintype "input"))
    )
    (net (code "32") (name "MOSI") (class "Default")
      (node (ref "J2") (pin "4") (pinfunction "4_4") (pintype "passive"))
      (node (ref "U1") (pin "21") (pinfunction "(MOSI/PCINT2)PB2_21") (pintype "bidirectional"))
    )
    (net (code "33") (name "MTA") (class "Default")
      (node (ref "U1") (pin "56") (pinfunction "(A11)PC3_56") (pintype "bidirectional"))
      (node (ref "U5") (pin "3") (pinfunction "A_3") (pintype "input"))
    )
    (net (code "34") (name "MTB") (class "Default")
      (node (ref "U1") (pin "54") (pinfunction "(A9)PC1_54") (pintype "bidirectional"))
      (node (ref "U5") (pin "6") (pinfunction "B_6") (pintype "input"))
    )
    (net (code "35") (name "MTC") (class "Default")
      (node (ref "U1") (pin "53") (pinfunction "(A8)PC0_53") (pintype "bidirectional"))
      (node (ref "U5") (pin "7") (pinfunction "C_7") (pintype "input"))
    )
    (net (code "36") (name "MTD") (class "Default")
      (node (ref "U1") (pin "55") (pinfunction "(A10)PC2_55") (pintype "bidirectional"))
      (node (ref "U5") (pin "4") (pinfunction "D_4") (pintype "input"))
    )
    (net (code "37") (name "Net-(D1-PadA)") (class "Default")
      (node (ref "D1") (pin "A") (pinfunction "A_A") (pintype "passive"))
      (node (ref "R3") (pin "1") (pinfunction "1_1") (pintype "passive"))
    )
    (net (code "38") (name "Net-(D2-PadA)") (class "Default")
      (node (ref "D2") (pin "A") (pinfunction "A_A") (pintype "passive"))
      (node (ref "R4") (pin "1") (pinfunction "1_1") (pintype "passive"))
    )
    (net (code "39") (name "Net-(J3-Pad1)") (class "Default")
      (node (ref "J3") (pin "1") (pinfunction "1_1") (pintype "passive"))
      (node (ref "R16") (pin "2") (pinfunction "2_2") (pintype "passive"))
    )
    (net (code "40") (name "Net-(J3-Pad2)") (class "Default")
      (node (ref "J3") (pin "2") (pinfunction "2_2") (pintype "passive"))
      (node (ref "J4") (pin "2") (pinfunction "2_2") (pintype "passive"))
    )
    (net (code "41") (name "Net-(N1-PadA)") (class "Default")
      (node (ref "N1") (pin "A") (pinfunction "A_A") (pintype "bidirectional"))
      (node (ref "R12") (pin "2") (pinfunction "2_2") (pintype "passive"))
    )
    (net (code "42") (name "Net-(N2-PadA)") (class "Default")
      (node (ref "N2") (pin "A") (pinfunction "A_A") (pintype "bidirectional"))
      (node (ref "R13") (pin "2") (pinfunction "2_2") (pintype "passive"))
    )
    (net (code "43") (name "Net-(N3-PadA)") (class "Default")
      (node (ref "N3") (pin "A") (pinfunction "A_A") (pintype "bidirectional"))
      (node (ref "R14") (pin "2") (pinfunction "2_2") (pintype "passive"))
    )
    (net (code "44") (name "Net-(N4-PadA)") (class "Default")
      (node (ref "N4") (pin "A") (pinfunction "A_A") (pintype "bidirectional"))
      (node (ref "R15") (pin "2") (pinfunction "2_2") (pintype "passive"))
    )
    (net (code "45") (name "Net-(R8-Pad2)") (class "Default")
      (node (ref "R8") (pin "2") (pinfunction "2_2") (pintype "passive"))
      (node (ref "R9") (pin "1") (pinfunction "1_1") (pintype "passive"))
    )
    (net (code "46") (name "Net-(R9-Pad2)") (class "Default")
      (node (ref "R9") (pin "2") (pinfunction "2_2") (pintype "passive"))
      (node (ref "T2") (pin "2") (pinfunction "C_2") (pintype "passive"))
      (node (ref "T2") (pin "4") (pinfunction "C_4") (pintype "passive"))
    )
    (net (code "47") (name "Net-(T1-B)") (class "Default")
      (node (ref "R7") (pin "1") (pinfunction "1_1") (pintype "passive"))
      (node (ref "R8") (pin "1") (pinfunction "1_1") (pintype "passive"))
      (node (ref "T1") (pin "1") (pinfunction "B_1") (pintype "passive"))
    )
    (net (code "48") (name "Net-(T1-E)") (class "Default")
      (node (ref "170V") (pin "TP") (pinfunction "TP_TP") (pintype "input"))
      (node (ref "C14") (pin "+") (pinfunction "+_+") (pintype "passive"))
      (node (ref "R7") (pin "2") (pinfunction "2_2") (pintype "passive"))
      (node (ref "T1") (pin "3") (pinfunction "E_3") (pintype "passive"))
      (node (ref "U7") (pin "2") (pinfunction "VOUT_2") (pintype "bidirectional"))
    )
    (net (code "49") (name "Net-(T2-B)") (class "Default")
      (node (ref "R10") (pin "1") (pinfunction "1_1") (pintype "passive"))
      (node (ref "T2") (pin "1") (pinfunction "B_1") (pintype "passive"))
    )
    (net (code "50") (name "Net-(T3-G)") (class "Default")
      (node (ref "T3") (pin "4") (pinfunction "G_4") (pintype "passive"))
      (node (ref "U12") (pin "1") (pinfunction "VBUSG_1") (pintype "bidirectional"))
    )
    (net (code "51") (name "Net-(U1-XTAL1)") (class "Default")
      (node (ref "R2") (pin "2") (pinfunction "2_2") (pintype "passive"))
      (node (ref "U1") (pin "34") (pinfunction "XTAL1_34") (pintype "input"))
      (node (ref "X1") (pin "3") (pinfunction "3_3") (pintype "passive"))
    )
    (net (code "52") (name "Net-(U1-XTAL2)") (class "Default")
      (node (ref "R2") (pin "1") (pinfunction "1_1") (pintype "passive"))
      (node (ref "U1") (pin "33") (pinfunction "XTAL2_33") (pintype "output"))
      (node (ref "X1") (pin "1") (pinfunction "1_1") (pintype "passive"))
    )
    (net (code "53") (name "Net-(U2-R232)") (class "Default")
      (node (ref "C5") (pin "1") (pinfunction "1_1") (pintype "passive"))
      (node (ref "U2") (pin "15") (pinfunction "R232_15") (pintype "bidirectional"))
    )
    (net (code "54") (name "Net-(U2-V3)") (class "Default")
      (node (ref "C6") (pin "1") (pinfunction "1_1") (pintype "passive"))
      (node (ref "U2") (pin "4") (pinfunction "V3_4") (pintype "bidirectional"))
    )
    (net (code "55") (name "Net-(U3-0)") (class "Default")
      (node (ref "N1") (pin "0") (pinfunction "0_0") (pintype "bidirectional"))
      (node (ref "U3") (pin "16") (pinfunction "0_16") (pintype "bidirectional"))
    )
    (net (code "56") (name "Net-(U3-1)") (class "Default")
      (node (ref "N1") (pin "1") (pinfunction "1_1") (pintype "bidirectional"))
      (node (ref "U3") (pin "15") (pinfunction "1_15") (pintype "bidirectional"))
    )
    (net (code "57") (name "Net-(U3-2)") (class "Default")
      (node (ref "N1") (pin "2") (pinfunction "2_2") (pintype "bidirectional"))
      (node (ref "U3") (pin "8") (pinfunction "2_8") (pintype "bidirectional"))
    )
    (net (code "58") (name "Net-(U3-3)") (class "Default")
      (node (ref "N1") (pin "3") (pinfunction "3_3") (pintype "bidirectional"))
      (node (ref "U3") (pin "9") (pinfunction "3_9") (pintype "bidirectional"))
    )
    (net (code "59") (name "Net-(U3-4)") (class "Default")
      (node (ref "N1") (pin "4") (pinfunction "4_4") (pintype "bidirectional"))
      (node (ref "U3") (pin "13") (pinfunction "4_13") (pintype "bidirectional"))
    )
    (net (code "60") (name "Net-(U3-5)") (class "Default")
      (node (ref "N1") (pin "5") (pinfunction "5_5") (pintype "bidirectional"))
      (node (ref "U3") (pin "14") (pinfunction "5_14") (pintype "bidirectional"))
    )
    (net (code "61") (name "Net-(U3-6)") (class "Default")
      (node (ref "N1") (pin "6") (pinfunction "6_6") (pintype "bidirectional"))
      (node (ref "U3") (pin "11") (pinfunction "6_11") (pintype "bidirectional"))
    )
    (net (code "62") (name "Net-(U3-7)") (class "Default")
      (node (ref "N1") (pin "7") (pinfunction "7_7") (pintype "bidirectional"))
      (node (ref "U3") (pin "10") (pinfunction "7_10") (pintype "bidirectional"))
    )
    (net (code "63") (name "Net-(U3-8)") (class "Default")
      (node (ref "N1") (pin "8") (pinfunction "8_8") (pintype "bidirectional"))
      (node (ref "U3") (pin "1") (pinfunction "8_1") (pintype "bidirectional"))
    )
    (net (code "64") (name "Net-(U3-9)") (class "Default")
      (node (ref "N1") (pin "9") (pinfunction "9_9") (pintype "bidirectional"))
      (node (ref "U3") (pin "2") (pinfunction "9_2") (pintype "bidirectional"))
    )
    (net (code "65") (name "Net-(U4-0)") (class "Default")
      (node (ref "N2") (pin "0") (pinfunction "0_0") (pintype "bidirectional"))
      (node (ref "U4") (pin "16") (pinfunction "0_16") (pintype "bidirectional"))
    )
    (net (code "66") (name "Net-(U4-1)") (class "Default")
      (node (ref "N2") (pin "1") (pinfunction "1_1") (pintype "bidirectional"))
      (node (ref "U4") (pin "15") (pinfunction "1_15") (pintype "bidirectional"))
    )
    (net (code "67") (name "Net-(U4-2)") (class "Default")
      (node (ref "N2") (pin "2") (pinfunction "2_2") (pintype "bidirectional"))
      (node (ref "U4") (pin "8") (pinfunction "2_8") (pintype "bidirectional"))
    )
    (net (code "68") (name "Net-(U4-3)") (class "Default")
      (node (ref "N2") (pin "3") (pinfunction "3_3") (pintype "bidirectional"))
      (node (ref "U4") (pin "9") (pinfunction "3_9") (pintype "bidirectional"))
    )
    (net (code "69") (name "Net-(U4-4)") (class "Default")
      (node (ref "N2") (pin "4") (pinfunction "4_4") (pintype "bidirectional"))
      (node (ref "U4") (pin "13") (pinfunction "4_13") (pintype "bidirectional"))
    )
    (net (code "70") (name "Net-(U4-5)") (class "Default")
      (node (ref "N2") (pin "5") (pinfunction "5_5") (pintype "bidirectional"))
      (node (ref "U4") (pin "14") (pinfunction "5_14") (pintype "bidirectional"))
    )
    (net (code "71") (name "Net-(U4-6)") (class "Default")
      (node (ref "N2") (pin "6") (pinfunction "6_6") (pintype "bidirectional"))
      (node (ref "U4") (pin "11") (pinfunction "6_11") (pintype "bidirectional"))
    )
    (net (code "72") (name "Net-(U4-7)") (class "Default")
      (node (ref "N2") (pin "7") (pinfunction "7_7") (pintype "bidirectional"))
      (node (ref "U4") (pin "10") (pinfunction "7_10") (pintype "bidirectional"))
    )
    (net (code "73") (name "Net-(U4-8)") (class "Default")
      (node (ref "N2") (pin "8") (pinfunction "8_8") (pintype "bidirectional"))
      (node (ref "U4") (pin "1") (pinfunction "8_1") (pintype "bidirectional"))
    )
    (net (code "74") (name "Net-(U4-9)") (class "Default")
      (node (ref "N2") (pin "9") (pinfunction "9_9") (pintype "bidirectional"))
      (node (ref "U4") (pin "2") (pinfunction "9_2") (pintype "bidirectional"))
    )
    (net (code "75") (name "Net-(U5-0)") (class "Default")
      (node (ref "N3") (pin "0") (pinfunction "0_0") (pintype "bidirectional"))
      (node (ref "U5") (pin "16") (pinfunction "0_16") (pintype "bidirectional"))
    )
    (net (code "76") (name "Net-(U5-1)") (class "Default")
      (node (ref "N3") (pin "1") (pinfunction "1_1") (pintype "bidirectional"))
      (node (ref "U5") (pin "15") (pinfunction "1_15") (pintype "bidirectional"))
    )
    (net (code "77") (name "Net-(U5-2)") (class "Default")
      (node (ref "N3") (pin "2") (pinfunction "2_2") (pintype "bidirectional"))
      (node (ref "U5") (pin "8") (pinfunction "2_8") (pintype "bidirectional"))
    )
    (net (code "78") (name "Net-(U5-3)") (class "Default")
      (node (ref "N3") (pin "3") (pinfunction "3_3") (pintype "bidirectional"))
      (node (ref "U5") (pin "9") (pinfunction "3_9") (pintype "bidirectional"))
    )
    (net (code "79") (name "Net-(U5-4)") (class "Default")
      (node (ref "N3") (pin "4") (pinfunction "4_4") (pintype "bidirectional"))
      (node (ref "U5") (pin "13") (pinfunction "4_13") (pintype "bidirectional"))
    )
    (net (code "80") (name "Net-(U5-5)") (class "Default")
      (node (ref "N3") (pin "5") (pinfunction "5_5") (pintype "bidirectional"))
      (node (ref "U5") (pin "14") (pinfunction "5_14") (pintype "bidirectional"))
    )
    (net (code "81") (name "Net-(U5-6)") (class "Default")
      (node (ref "N3") (pin "6") (pinfunction "6_6") (pintype "bidirectional"))
      (node (ref "U5") (pin "11") (pinfunction "6_11") (pintype "bidirectional"))
    )
    (net (code "82") (name "Net-(U5-7)") (class "Default")
      (node (ref "N3") (pin "7") (pinfunction "7_7") (pintype "bidirectional"))
      (node (ref "U5") (pin "10") (pinfunction "7_10") (pintype "bidirectional"))
    )
    (net (code "83") (name "Net-(U5-8)") (class "Default")
      (node (ref "N3") (pin "8") (pinfunction "8_8") (pintype "bidirectional"))
      (node (ref "U5") (pin "1") (pinfunction "8_1") (pintype "bidirectional"))
    )
    (net (code "84") (name "Net-(U5-9)") (class "Default")
      (node (ref "N3") (pin "9") (pinfunction "9_9") (pintype "bidirectional"))
      (node (ref "U5") (pin "2") (pinfunction "9_2") (pintype "bidirectional"))
    )
    (net (code "85") (name "Net-(U6-0)") (class "Default")
      (node (ref "N4") (pin "0") (pinfunction "0_0") (pintype "bidirectional"))
      (node (ref "U6") (pin "16") (pinfunction "0_16") (pintype "bidirectional"))
    )
    (net (code "86") (name "Net-(U6-1)") (class "Default")
      (node (ref "N4") (pin "1") (pinfunction "1_1") (pintype "bidirectional"))
      (node (ref "U6") (pin "15") (pinfunction "1_15") (pintype "bidirectional"))
    )
    (net (code "87") (name "Net-(U6-2)") (class "Default")
      (node (ref "N4") (pin "2") (pinfunction "2_2") (pintype "bidirectional"))
      (node (ref "U6") (pin "8") (pinfunction "2_8") (pintype "bidirectional"))
    )
    (net (code "88") (name "Net-(U6-3)") (class "Default")
      (node (ref "N4") (pin "3") (pinfunction "3_3") (pintype "bidirectional"))
      (node (ref "U6") (pin "9") (pinfunction "3_9") (pintype "bidirectional"))
    )
    (net (code "89") (name "Net-(U6-4)") (class "Default")
      (node (ref "N4") (pin "4") (pinfunction "4_4") (pintype "bidirectional"))
      (node (ref "U6") (pin "13") (pinfunction "4_13") (pintype "bidirectional"))
    )
    (net (code "90") (name "Net-(U6-5)") (class "Default")
      (node (ref "N4") (pin "5") (pinfunction "5_5") (pintype "bidirectional"))
      (node (ref "U6") (pin "14") (pinfunction "5_14") (pintype "bidirectional"))
    )
    (net (code "91") (name "Net-(U6-6)") (class "Default")
      (node (ref "N4") (pin "6") (pinfunction "6_6") (pintype "bidirectional"))
      (node (ref "U6") (pin "11") (pinfunction "6_11") (pintype "bidirectional"))
    )
    (net (code "92") (name "Net-(U6-7)") (class "Default")
      (node (ref "N4") (pin "7") (pinfunction "7_7") (pintype "bidirectional"))
      (node (ref "U6") (pin "10") (pinfunction "7_10") (pintype "bidirectional"))
    )
    (net (code "93") (name "Net-(U6-8)") (class "Default")
      (node (ref "N4") (pin "8") (pinfunction "8_8") (pintype "bidirectional"))
      (node (ref "U6") (pin "1") (pinfunction "8_1") (pintype "bidirectional"))
    )
    (net (code "94") (name "Net-(U6-9)") (class "Default")
      (node (ref "N4") (pin "9") (pinfunction "9_9") (pintype "bidirectional"))
      (node (ref "U6") (pin "2") (pinfunction "9_2") (pintype "bidirectional"))
    )
    (net (code "95") (name "Net-(U8-VBAT)") (class "Default")
      (node (ref "BATTERY") (pin "TP") (pinfunction "TP_TP") (pintype "input"))
      (node (ref "BT1") (pin "+") (pinfunction "+_+") (pintype "passive"))
      (node (ref "U8") (pin "14") (pinfunction "VBAT_14") (pintype "power_in"))
    )
    (net (code "96") (name "Net-(U10-OUT)") (class "Default")
      (node (ref "C10") (pin "1") (pinfunction "1_1") (pintype "passive"))
      (node (ref "C11") (pin "1") (pinfunction "1_1") (pintype "passive"))
      (node (ref "C9") (pin "1") (pinfunction "1_1") (pintype "passive"))
      (node (ref "GPS_PWR") (pin "TP") (pinfunction "TP_TP") (pintype "input"))
      (node (ref "U10") (pin "5") (pinfunction "OUT_5") (pintype "output"))
      (node (ref "U11") (pin "4") (pinfunction "VCC_4") (pintype "power_in"))
      (node (ref "U11") (pin "5") (pinfunction "V_BCKP_5") (pintype "power_in"))
    )
    (net (code "97") (name "Net-(U11-RXD1)") (class "Default")
      (node (ref "R19") (pin "2") (pinfunction "2_2") (pintype "passive"))
      (node (ref "R20") (pin "2") (pinfunction "2_2") (pintype "passive"))
      (node (ref "RX") (pin "TP") (pinfunction "TP_TP") (pintype "input"))
      (node (ref "U11") (pin "1") (pinfunction "RXD1_1") (pintype "input"))
    )
    (net (code "98") (name "Net-(U12-SEL)") (class "Default")
      (node (ref "SJ1") (pin "2") (pinfunction "2_2") (pintype "passive"))
      (node (ref "U12") (pin "11") (pinfunction "SEL_11") (pintype "bidirectional"))
    )
    (net (code "99") (name "ONE") (class "Default")
      (node (ref "S1") (pin "10") (pinfunction "10_10") (pintype "passive"))
      (node (ref "U1") (pin "77") (pinfunction "(AD1)PA1_77") (pintype "bidirectional"))
    )
    (net (code "100") (name "PLUS_MINUS") (class "Default")
      (node (ref "S1") (pin "14") (pinfunction "14_14") (pintype "passive"))
      (node (ref "U1") (pin "73") (pinfunction "(AD5)PA5_73") (pintype "bidirectional"))
    )
    (net (code "101") (name "RST") (class "Default")
      (node (ref "C1") (pin "2") (pinfunction "2_2") (pintype "passive"))
      (node (ref "J2") (pin "5") (pinfunction "5_5") (pintype "passive"))
      (node (ref "R1") (pin "1") (pinfunction "1_1") (pintype "passive"))
      (node (ref "U1") (pin "30") (pinfunction "RESET_30") (pintype "input"))
    )
    (net (code "102") (name "RTC_INT") (class "Default")
      (node (ref "RTC_INT") (pin "TP") (pinfunction "TP_TP") (pintype "input"))
      (node (ref "U1") (pin "6") (pinfunction "(OC3B/INT4)PE4_6") (pintype "bidirectional"))
      (node (ref "U8") (pin "3") (pinfunction "SQW/~{INT}_3") (pintype "output"))
    )
    (net (code "103") (name "RXI") (class "Default")
      (node (ref "D1") (pin "C") (pinfunction "C_C") (pintype "passive"))
      (node (ref "J1") (pin "P$3") (pinfunction "RXI_P$3") (pintype "passive"))
      (node (ref "U1") (pin "3") (pinfunction "(TXD0)PE1_3") (pintype "bidirectional"))
      (node (ref "U2") (pin "3") (pinfunction "RXI_3") (pintype "bidirectional"))
    )
    (net (code "104") (name "SCK") (class "Default")
      (node (ref "J2") (pin "3") (pinfunction "3_3") (pintype "passive"))
      (node (ref "U1") (pin "20") (pinfunction "(SCK/PCINT1)PB1_20") (pintype "bidirectional"))
    )
    (net (code "105") (name "SCL") (class "Default")
      (node (ref "R18") (pin "1") (pinfunction "1_1") (pintype "passive"))
      (node (ref "SCL") (pin "TP") (pinfunction "TP_TP") (pintype "input"))
      (node (ref "U1") (pin "43") (pinfunction "(SCL/INT0)PD0_43") (pintype "bidirectional"))
      (node (ref "U8") (pin "16") (pinfunction "SCL_16") (pintype "input"))
    )
    (net (code "106") (name "SDA") (class "Default")
      (node (ref "R17") (pin "1") (pinfunction "1_1") (pintype "passive"))
      (node (ref "SDA") (pin "TP") (pinfunction "TP_TP") (pintype "input"))
      (node (ref "U1") (pin "44") (pinfunction "(SDA/INT1)PD1_44") (pintype "bidirectional"))
      (node (ref "U8") (pin "15") (pinfunction "SDA_15") (pintype "bidirectional"))
    )
    (net (code "107") (name "TIME_MODE") (class "Default")
      (node (ref "S1") (pin "15") (pinfunction "15_15") (pintype "passive"))
      (node (ref "U1") (pin "72") (pinfunction "(AD6)PA6_72") (pintype "bidirectional"))
    )
    (net (code "108") (name "TWO") (class "Default")
      (node (ref "S1") (pin "11") (pinfunction "11_11") (pintype "passive"))
      (node (ref "U1") (pin "76") (pinfunction "(AD2)PA2_76") (pintype "bidirectional"))
    )
    (net (code "109") (name "TXO") (class "Default")
      (node (ref "D2") (pin "C") (pinfunction "C_C") (pintype "passive"))
      (node (ref "J1") (pin "P$2") (pinfunction "TXO_P$2") (pintype "passive"))
      (node (ref "U1") (pin "2") (pinfunction "(RXD0/PCIN8)PE0_2") (pintype "bidirectional"))
      (node (ref "U2") (pin "2") (pinfunction "TXO_2") (pintype "bidirectional"))
    )
    (net (code "110") (name "VCCA") (class "Default")
      (node (ref "5V_ANALOG") (pin "TP") (pinfunction "TP_TP") (pintype "input"))
      (node (ref "PH1") (pin "1") (pinfunction "1_1") (pintype "passive"))
      (node (ref "U1") (pin "100") (pinfunction "AVCC_100") (pintype "power_in"))
      (node (ref "U1") (pin "98") (pinfunction "AREF_98") (pintype "bidirectional"))
      (node (ref "U14") (pin "3") (pinfunction "VO_3") (pintype "passive"))
    )
    (net (code "111") (name "VOUT") (class "Default")
      (node (ref "C13") (pin "1") (pinfunction "1_1") (pintype "passive"))
      (node (ref "C16") (pin "1") (pinfunction "1_1") (pintype "passive"))
      (node (ref "C17") (pin "1") (pinfunction "1_1") (pintype "passive"))
      (node (ref "C18") (pin "1") (pinfunction "1_1") (pintype "passive"))
      (node (ref "T3") (pin "10") (pinfunction "D_10") (pintype "passive"))
      (node (ref "T3") (pin "11") (pinfunction "D_11") (pintype "passive"))
      (node (ref "T3") (pin "12") (pinfunction "D_12") (pintype "passive"))
      (node (ref "T3") (pin "5") (pinfunction "D_5") (pintype "passive"))
      (node (ref "T3") (pin "6") (pinfunction "D_6") (pintype "passive"))
      (node (ref "T3") (pin "7") (pinfunction "D_7") (pintype "passive"))
      (node (ref "T3") (pin "8") (pinfunction "D_8") (pintype "passive"))
      (node (ref "T3") (pin "9") (pinfunction "D_9") (pintype "passive"))
      (node (ref "U12") (pin "16") (pinfunction "VBUS_16") (pintype "bidirectional"))
      (node (ref "U13") (pin "1") (pinfunction "VI_1") (pintype "input"))
      (node (ref "U14") (pin "1") (pinfunction "VI_1") (pintype "input"))
      (node (ref "U7") (pin "1") (pinfunction "VCC_1") (pintype "bidirectional"))
      (node (ref "VOUT") (pin "TP") (pinfunction "TP_TP") (pintype "input"))
    )
    (net (code "112") (name "V_USB") (class "Default")
      (node (ref "C15") (pin "1") (pinfunction "1_1") (pintype "passive"))
      (node (ref "J5") (pin "A4B9") (pinfunction "VBUS_A4B9") (pintype "power_in"))
      (node (ref "J5") (pin "B4A9") (pinfunction "VBUS_B4A9") (pintype "power_in"))
      (node (ref "SJ1") (pin "1") (pinfunction "1_1") (pintype "passive"))
      (node (ref "T3") (pin "1") (pinfunction "S_1") (pintype "passive"))
      (node (ref "T3") (pin "2") (pinfunction "S_2") (pintype "passive"))
      (node (ref "T3") (pin "3") (pinfunction "S_3") (pintype "passive"))
      (node (ref "U12") (pin "2") (pinfunction "VIN_2") (pintype "bidirectional"))
      (node (ref "V_USB") (pin "TP") (pinfunction "TP_TP") (pintype "input"))
    )
    (net (code "113") (name "unconnected-(J5-SBU1-PadA8)") (class "Default")
      (node (ref "J5") (pin "A8") (pinfunction "SBU1_A8") (pintype "bidirectional"))
    )
    (net (code "114") (name "unconnected-(J5-SBU2-PadB8)") (class "Default")
      (node (ref "J5") (pin "B8") (pinfunction "SBU2_B8") (pintype "bidirectional"))
    )
    (net (code "115") (name "unconnected-(U1-(ADC1)PF1-Pad96)") (class "Default")
      (node (ref "U1") (pin "96") (pinfunction "(ADC1)PF1_96") (pintype "bidirectional"))
    )
    (net (code "116") (name "unconnected-(U1-(ADC2)PF2-Pad95)") (class "Default")
      (node (ref "U1") (pin "95") (pinfunction "(ADC2)PF2_95") (pintype "bidirectional"))
    )
    (net (code "117") (name "unconnected-(U1-(ADC3)PF3-Pad94)") (class "Default")
      (node (ref "U1") (pin "94") (pinfunction "(ADC3)PF3_94") (pintype "bidirectional"))
    )
    (net (code "118") (name "unconnected-(U1-(ADC4{slash}TCK)PF4-Pad93)") (class "Default")
      (node (ref "U1") (pin "93") (pinfunction "(ADC4/TCK)PF4_93") (pintype "bidirectional"))
    )
    (net (code "119") (name "unconnected-(U1-(ADC5{slash}TMS)PF5-Pad92)") (class "Default")
      (node (ref "U1") (pin "92") (pinfunction "(ADC5/TMS)PF5_92") (pintype "bidirectional"))
    )
    (net (code "120") (name "unconnected-(U1-(ADC6{slash}TDO)PF6-Pad91)") (class "Default")
      (node (ref "U1") (pin "91") (pinfunction "(ADC6/TDO)PF6_91") (pintype "bidirectional"))
    )
    (net (code "121") (name "unconnected-(U1-(ADC7{slash}TDI)PF7-Pad90)") (class "Default")
      (node (ref "U1") (pin "90") (pinfunction "(ADC7/TDI)PF7_90") (pintype "bidirectional"))
    )
    (net (code "122") (name "unconnected-(U1-(CLKO{slash}ICP3{slash}INT7)PE7-Pad9)") (class "Default")
      (node (ref "U1") (pin "9") (pinfunction "(CLKO/ICP3/INT7)PE7_9") (pintype "bidirectional"))
    )
    (net (code "123") (name "unconnected-(U1-(ICP1)PD4-Pad47)") (class "Default")
      (node (ref "U1") (pin "47") (pinfunction "(ICP1)PD4_47") (pintype "bidirectional"))
    )
    (net (code "124") (name "unconnected-(U1-(OC0A{slash}OC1C{slash}PCINT7)PB7-Pad26)") (class "Default")
      (node (ref "U1") (pin "26") (pinfunction "(OC0A/OC1C/PCINT7)PB7_26") (pintype "bidirectional"))
    )
    (net (code "125") (name "unconnected-(U1-(OC1A{slash}PCINT5)PB5-Pad24)") (class "Default")
      (node (ref "U1") (pin "24") (pinfunction "(OC1A/PCINT5)PB5_24") (pintype "bidirectional"))
    )
    (net (code "126") (name "unconnected-(U1-(OC1B{slash}PCINT6)PB6-Pad25)") (class "Default")
      (node (ref "U1") (pin "25") (pinfunction "(OC1B/PCINT6)PB6_25") (pintype "bidirectional"))
    )
    (net (code "127") (name "unconnected-(U1-(OC2A{slash}PCINT4)PB4-Pad23)") (class "Default")
      (node (ref "U1") (pin "23") (pinfunction "(OC2A/PCINT4)PB4_23") (pintype "bidirectional"))
    )
    (net (code "128") (name "unconnected-(U1-(OC3A{slash}AIN1)PE3-Pad5)") (class "Default")
      (node (ref "U1") (pin "5") (pinfunction "(OC3A/AIN1)PE3_5") (pintype "bidirectional"))
    )
    (net (code "129") (name "unconnected-(U1-(OC3C{slash}INT5)PE5-Pad7)") (class "Default")
      (node (ref "U1") (pin "7") (pinfunction "(OC3C/INT5)PE5_7") (pintype "bidirectional"))
    )
    (net (code "130") (name "unconnected-(U1-(RD)PG1-Pad52)") (class "Default")
      (node (ref "U1") (pin "52") (pinfunction "(RD)PG1_52") (pintype "bidirectional"))
    )
    (net (code "131") (name "unconnected-(U1-(RXD1{slash}INT2)PD2-Pad45)") (class "Default")
      (node (ref "U1") (pin "45") (pinfunction "(RXD1/INT2)PD2_45") (pintype "bidirectional"))
    )
    (net (code "132") (name "unconnected-(U1-(SS{slash}PCINT0)PB0-Pad19)") (class "Default")
      (node (ref "U1") (pin "19") (pinfunction "(SS/PCINT0)PB0_19") (pintype "bidirectional"))
    )
    (net (code "133") (name "unconnected-(U1-(T0)PD7-Pad50)") (class "Default")
      (node (ref "U1") (pin "50") (pinfunction "(T0)PD7_50") (pintype "bidirectional"))
    )
    (net (code "134") (name "unconnected-(U1-(T1)PD6-Pad49)") (class "Default")
      (node (ref "U1") (pin "49") (pinfunction "(T1)PD6_49") (pintype "bidirectional"))
    )
    (net (code "135") (name "unconnected-(U1-(T3{slash}INT6)PE6-Pad8)") (class "Default")
      (node (ref "U1") (pin "8") (pinfunction "(T3/INT6)PE6_8") (pintype "bidirectional"))
    )
    (net (code "136") (name "unconnected-(U1-(TOSC1)PG4-Pad29)") (class "Default")
      (node (ref "U1") (pin "29") (pinfunction "(TOSC1)PG4_29") (pintype "bidirectional"))
    )
    (net (code "137") (name "unconnected-(U1-(TOSC2)PG3-Pad28)") (class "Default")
      (node (ref "U1") (pin "28") (pinfunction "(TOSC2)PG3_28") (pintype "bidirectional"))
    )
    (net (code "138") (name "unconnected-(U1-(TXD1{slash}INT3)PD3-Pad46)") (class "Default")
      (node (ref "U1") (pin "46") (pinfunction "(TXD1/INT3)PD3_46") (pintype "bidirectional"))
    )
    (net (code "139") (name "unconnected-(U1-(WR)PG0-Pad51)") (class "Default")
      (node (ref "U1") (pin "51") (pinfunction "(WR)PG0_51") (pintype "bidirectional"))
    )
    (net (code "140") (name "unconnected-(U1-(XCK0{slash}AIN0)PE2-Pad4)") (class "Default")
      (node (ref "U1") (pin "4") (pinfunction "(XCK0/AIN0)PE2_4") (pintype "bidirectional"))
    )
    (net (code "141") (name "unconnected-(U1-(XCK1)PD5-Pad48)") (class "Default")
      (node (ref "U1") (pin "48") (pinfunction "(XCK1)PD5_48") (pintype "bidirectional"))
    )
    (net (code "142") (name "unconnected-(U1-PH0(RXD2)-Pad12)") (class "Default")
      (node (ref "U1") (pin "12") (pinfunction "PH0(RXD2)_12") (pintype "bidirectional"))
    )
    (net (code "143") (name "unconnected-(U1-PH1(TXD2)-Pad13)") (class "Default")
      (node (ref "U1") (pin "13") (pinfunction "PH1(TXD2)_13") (pintype "bidirectional"))
    )
    (net (code "144") (name "unconnected-(U1-PH2(XCK2)-Pad14)") (class "Default")
      (node (ref "U1") (pin "14") (pinfunction "PH2(XCK2)_14") (pintype "bidirectional"))
    )
    (net (code "145") (name "unconnected-(U1-PH3(OC4A)-Pad15)") (class "Default")
      (node (ref "U1") (pin "15") (pinfunction "PH3(OC4A)_15") (pintype "bidirectional"))
    )
    (net (code "146") (name "unconnected-(U1-PH4(OC4B)-Pad16)") (class "Default")
      (node (ref "U1") (pin "16") (pinfunction "PH4(OC4B)_16") (pintype "bidirectional"))
    )
    (net (code "147") (name "unconnected-(U1-PH5(OC4C)-Pad17)") (class "Default")
      (node (ref "U1") (pin "17") (pinfunction "PH5(OC4C)_17") (pintype "bidirectional"))
    )
    (net (code "148") (name "unconnected-(U1-PH6(OC2B)-Pad18)") (class "Default")
      (node (ref "U1") (pin "18") (pinfunction "PH6(OC2B)_18") (pintype "bidirectional"))
    )
    (net (code "149") (name "unconnected-(U1-PH7(T4)-Pad27)") (class "Default")
      (node (ref "U1") (pin "27") (pinfunction "PH7(T4)_27") (pintype "bidirectional"))
    )
    (net (code "150") (name "unconnected-(U1-PJ2(XCK3{slash}PCINT11)-Pad65)") (class "Default")
      (node (ref "U1") (pin "65") (pinfunction "PJ2(XCK3/PCINT11)_65") (pintype "bidirectional"))
    )
    (net (code "151") (name "unconnected-(U1-PJ3(PCINT12)-Pad66)") (class "Default")
      (node (ref "U1") (pin "66") (pinfunction "PJ3(PCINT12)_66") (pintype "bidirectional"))
    )
    (net (code "152") (name "unconnected-(U1-PJ4(PCINT13)-Pad67)") (class "Default")
      (node (ref "U1") (pin "67") (pinfunction "PJ4(PCINT13)_67") (pintype "bidirectional"))
    )
    (net (code "153") (name "unconnected-(U1-PJ5(PCINT14)-Pad68)") (class "Default")
      (node (ref "U1") (pin "68") (pinfunction "PJ5(PCINT14)_68") (pintype "bidirectional"))
    )
    (net (code "154") (name "unconnected-(U1-PJ6(PCINT15)-Pad69)") (class "Default")
      (node (ref "U1") (pin "69") (pinfunction "PJ6(PCINT15)_69") (pintype "bidirectional"))
    )
    (net (code "155") (name "unconnected-(U1-PJ7-Pad79)") (class "Default")
      (node (ref "U1") (pin "79") (pinfunction "PJ7_79") (pintype "bidirectional"))
    )
    (net (code "156") (name "unconnected-(U1-PK0(ADC8{slash}PCINT16)-Pad89)") (class "Default")
      (node (ref "U1") (pin "89") (pinfunction "PK0(ADC8/PCINT16)_89") (pintype "bidirectional"))
    )
    (net (code "157") (name "unconnected-(U1-PK1(ADC9{slash}PCINT17)-Pad88)") (class "Default")
      (node (ref "U1") (pin "88") (pinfunction "PK1(ADC9/PCINT17)_88") (pintype "bidirectional"))
    )
    (net (code "158") (name "unconnected-(U1-PK2(ADC10{slash}PCINT18)-Pad87)") (class "Default")
      (node (ref "U1") (pin "87") (pinfunction "PK2(ADC10/PCINT18)_87") (pintype "bidirectional"))
    )
    (net (code "159") (name "unconnected-(U1-PK3(ADC11{slash}PCINT19)-Pad86)") (class "Default")
      (node (ref "U1") (pin "86") (pinfunction "PK3(ADC11/PCINT19)_86") (pintype "bidirectional"))
    )
    (net (code "160") (name "unconnected-(U1-PK4(ADC12{slash}PCINT20)-Pad85)") (class "Default")
      (node (ref "U1") (pin "85") (pinfunction "PK4(ADC12/PCINT20)_85") (pintype "bidirectional"))
    )
    (net (code "161") (name "unconnected-(U1-PK5(ADC13{slash}PCINT21)-Pad84)") (class "Default")
      (node (ref "U1") (pin "84") (pinfunction "PK5(ADC13/PCINT21)_84") (pintype "bidirectional"))
    )
    (net (code "162") (name "unconnected-(U1-PK6(ADC14{slash}PCINT22)-Pad83)") (class "Default")
      (node (ref "U1") (pin "83") (pinfunction "PK6(ADC14/PCINT22)_83") (pintype "bidirectional"))
    )
    (net (code "163") (name "unconnected-(U1-PK7(ADC15{slash}PCINT23)-Pad82)") (class "Default")
      (node (ref "U1") (pin "82") (pinfunction "PK7(ADC15/PCINT23)_82") (pintype "bidirectional"))
    )
    (net (code "164") (name "unconnected-(U2-~{CTS}-Pad9)") (class "Default")
      (node (ref "U2") (pin "9") (pinfunction "~{CTS}_9") (pintype "bidirectional"))
    )
    (net (code "165") (name "unconnected-(U2-~{DCD}-Pad12)") (class "Default")
      (node (ref "U2") (pin "12") (pinfunction "~{DCD}_12") (pintype "bidirectional"))
    )
    (net (code "166") (name "unconnected-(U2-~{DSR}-Pad10)") (class "Default")
      (node (ref "U2") (pin "10") (pinfunction "~{DSR}_10") (pintype "bidirectional"))
    )
    (net (code "167") (name "unconnected-(U2-~{RI}-Pad11)") (class "Default")
      (node (ref "U2") (pin "11") (pinfunction "~{RI}_11") (pintype "bidirectional"))
    )
    (net (code "168") (name "unconnected-(U2-~{RTS}-Pad14)") (class "Default")
      (node (ref "U2") (pin "14") (pinfunction "~{RTS}_14") (pintype "bidirectional"))
    )
    (net (code "169") (name "unconnected-(U8-32KHZ-Pad1)") (class "Default")
      (node (ref "U8") (pin "1") (pinfunction "32KHZ_1") (pintype "output"))
    )
    (net (code "170") (name "unconnected-(U8-~{RST}-Pad4)") (class "Default")
      (node (ref "U8") (pin "4") (pinfunction "~{RST}_4") (pintype "input"))
    )
    (net (code "171") (name "unconnected-(U11-1PPS-Pad6)") (class "Default")
      (node (ref "U11") (pin "6") (pinfunction "1PPS_6") (pintype "output"))
    )
    (net (code "172") (name "unconnected-(U11-AADET_N-Pad8)") (class "Default")
      (node (ref "U11") (pin "8") (pinfunction "AADET_N_8") (pintype "bidirectional"))
    )
    (net (code "173") (name "unconnected-(U11-EX_ANT-Pad11)") (class "Default")
      (node (ref "U11") (pin "11") (pinfunction "EX_ANT_11") (pintype "input"))
    )
    (net (code "174") (name "unconnected-(U11-RESET-Pad10)") (class "Default")
      (node (ref "U11") (pin "10") (pinfunction "RESET_10") (pintype "input"))
    )
    (net (code "175") (name "unconnected-(U11-TIMER-Pad7)") (class "Default")
      (node (ref "U11") (pin "7") (pinfunction "TIMER_7") (pintype "output"))
    )
  )
)
